# Sheet1.net
KiCad netlist of a schematic drawn in Altium Designer
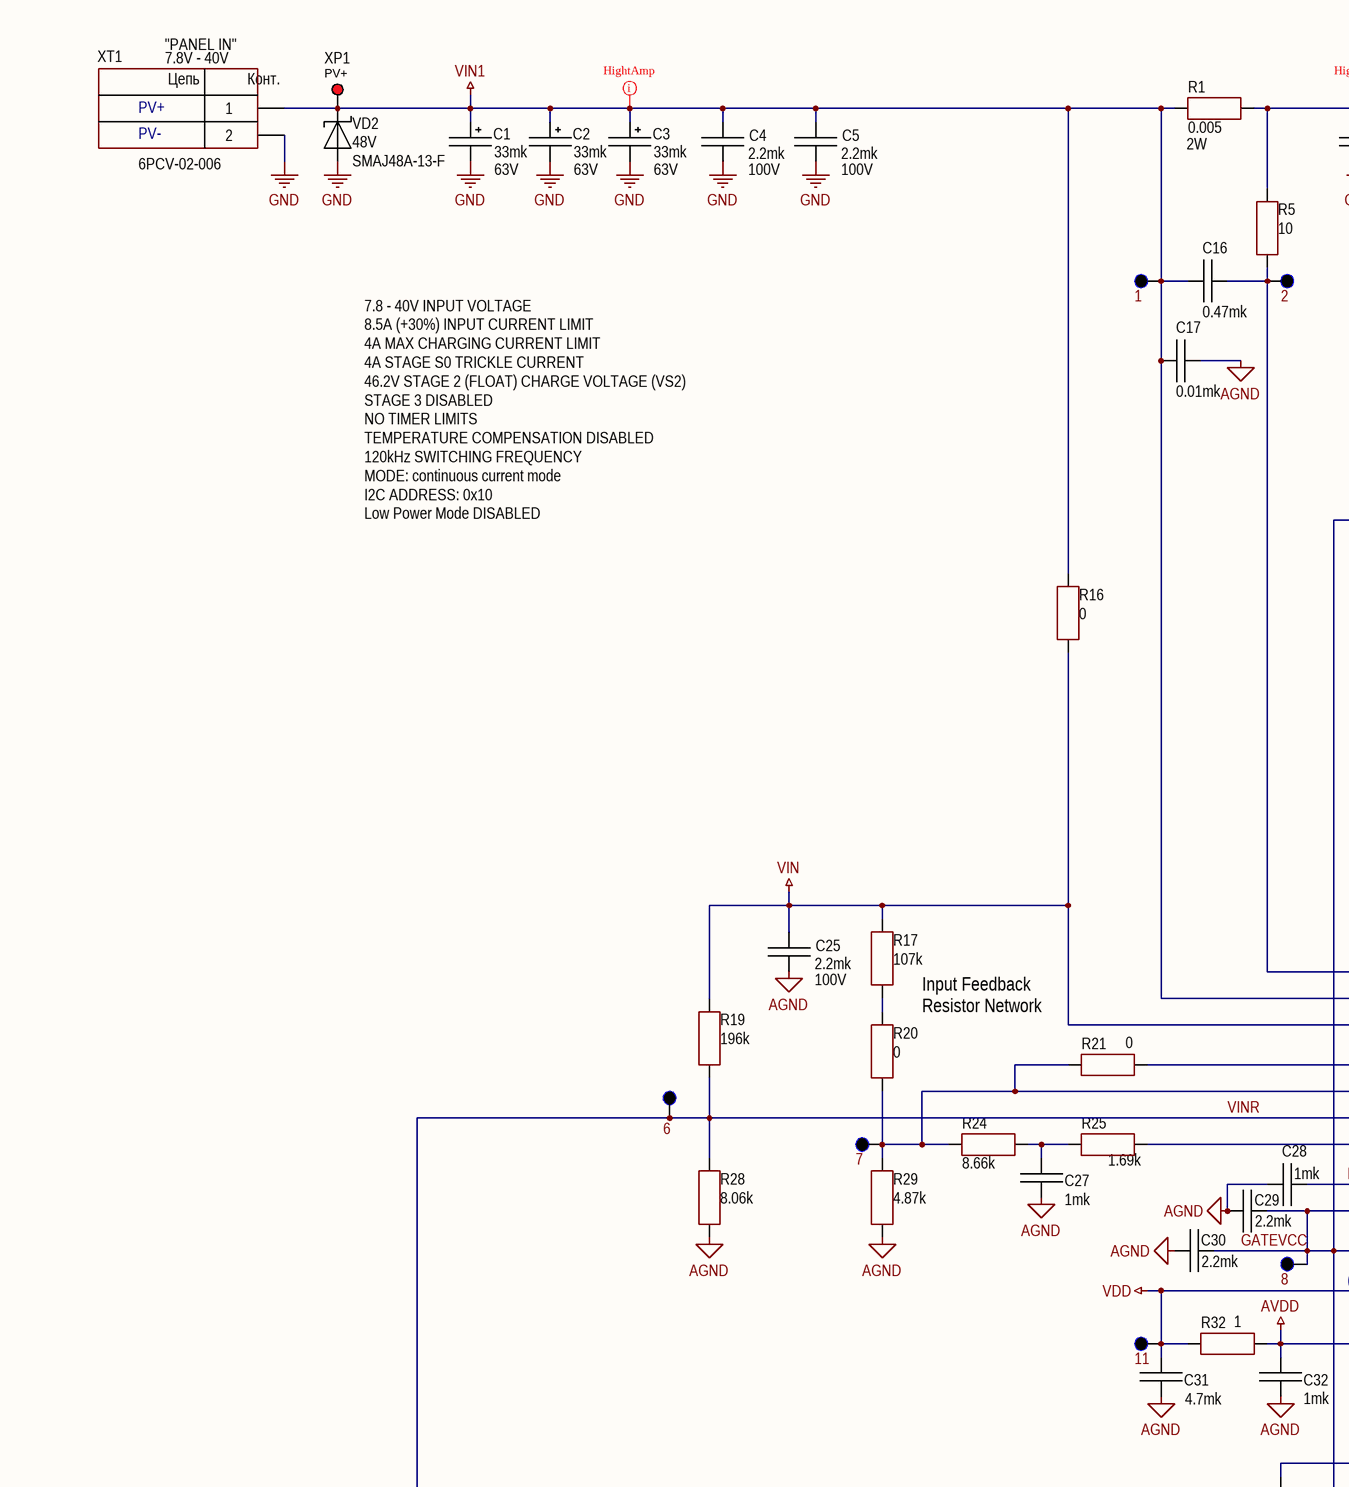
[diagram p0: Sheet1.SchDoc, top left]
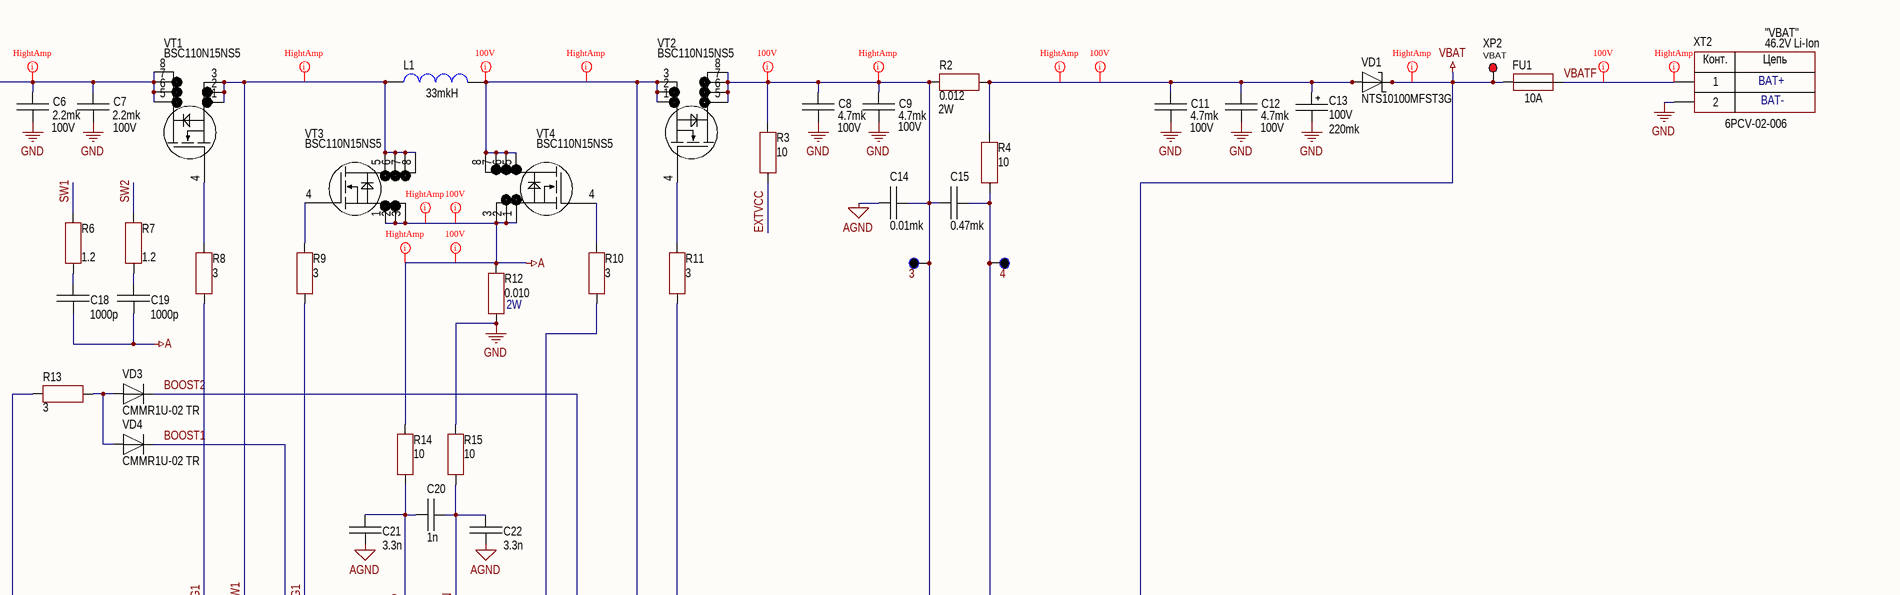
[diagram p1: Sheet1.SchDoc, top right]
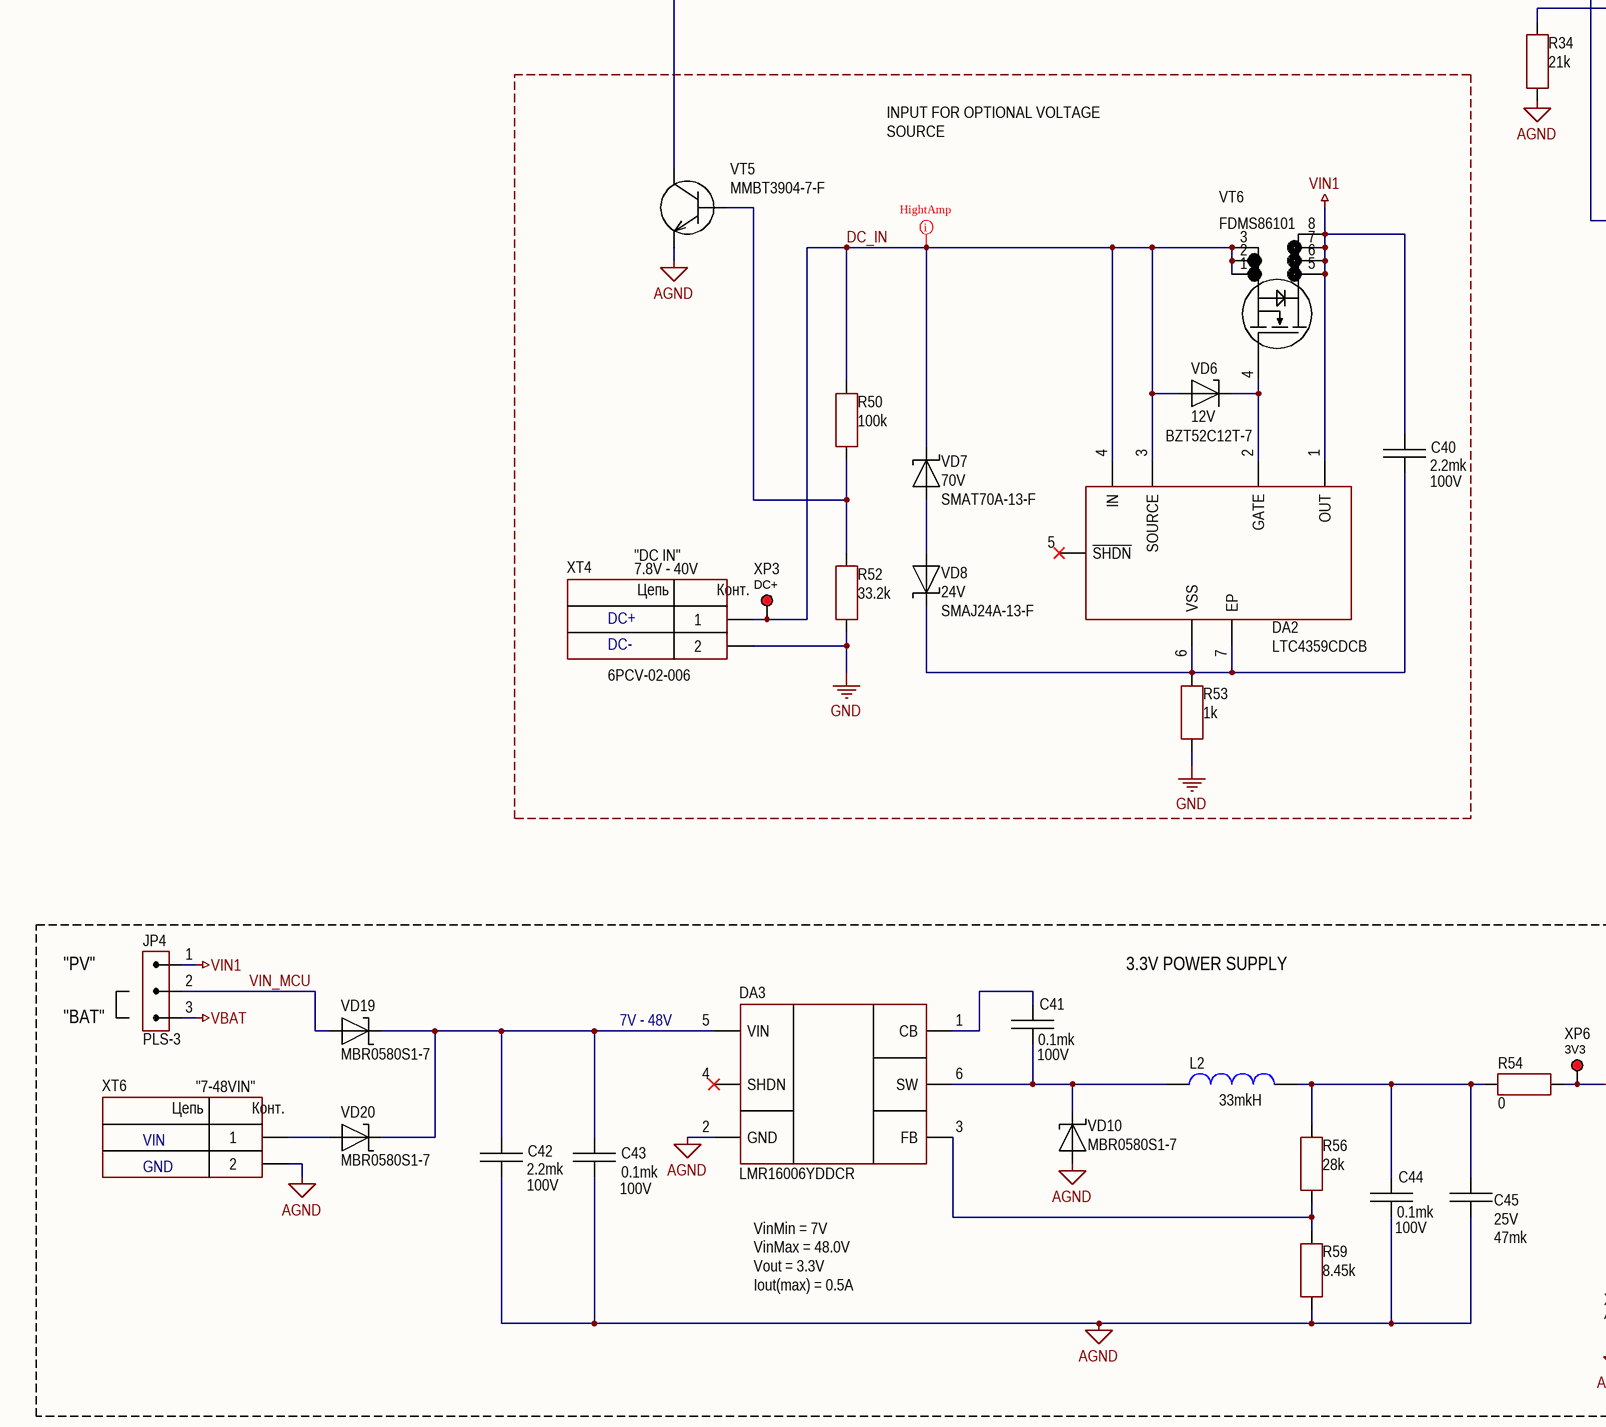
[diagram p2: Sheet1.SchDoc, bottom left]
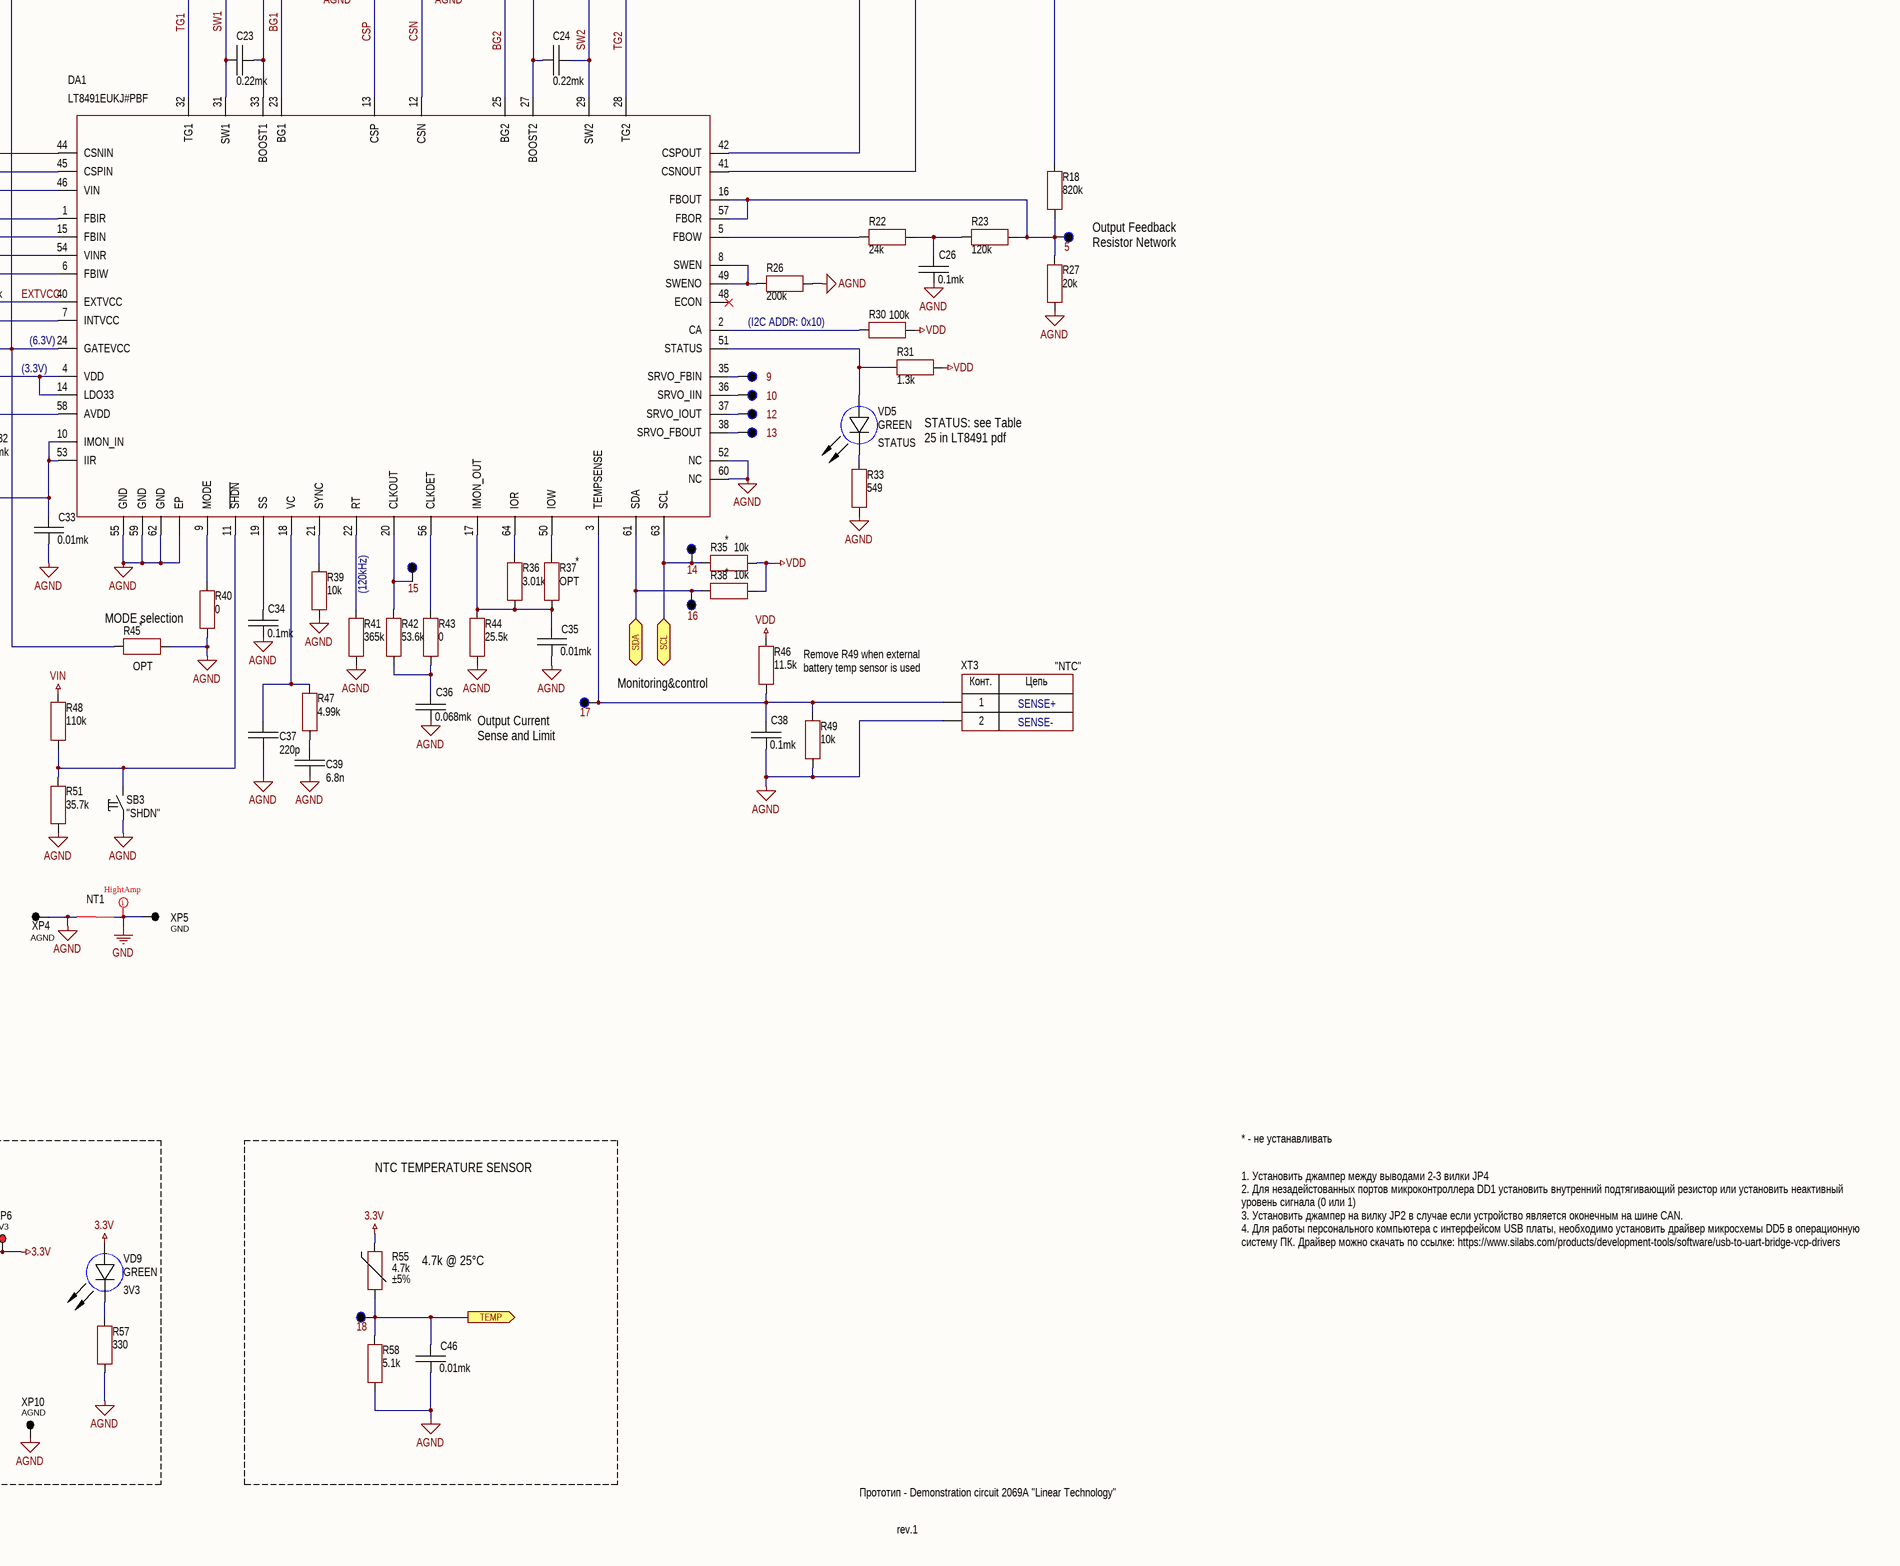
[diagram p3: Sheet1.SchDoc, bottom right]

(export (version "E")
  (design (tool "Eeschema 10.0.6"))
  (components
    (comp (ref "1")
      (value "test")
      (footprint "TEST_point_SMD")
      (description "Контактная площадка без компонента")
      (libsource (lib "Connector") (part "TEST point"))
    )
    (comp (ref "2")
      (value "test")
      (footprint "TEST_point_SMD")
      (description "Контактная площадка без компонента")
      (libsource (lib "Connector") (part "TEST point"))
    )
    (comp (ref "3")
      (value "test")
      (footprint "TEST_point_SMD")
      (description "Контактная площадка без компонента")
      (libsource (lib "Connector") (part "TEST point"))
    )
    (comp (ref "4")
      (value "test")
      (footprint "TEST_point_SMD")
      (description "Контактная площадка без компонента")
      (libsource (lib "Connector") (part "TEST point"))
    )
    (comp (ref "5")
      (value "test")
      (footprint "TEST_point_SMD")
      (description "Контактная площадка без компонента")
      (libsource (lib "Connector") (part "TEST point"))
    )
    (comp (ref "6")
      (value "test")
      (footprint "TEST_point_SMD")
      (description "Контактная площадка без компонента")
      (libsource (lib "Connector") (part "TEST point"))
    )
    (comp (ref "7")
      (value "test")
      (footprint "TEST_point_SMD")
      (description "Контактная площадка без компонента")
      (libsource (lib "Connector") (part "TEST point"))
    )
    (comp (ref "8")
      (value "test")
      (footprint "TEST_point_SMD")
      (description "Контактная площадка без компонента")
      (libsource (lib "Connector") (part "TEST point"))
    )
    (comp (ref "9")
      (value "test")
      (footprint "TEST_point_SMD")
      (description "Контактная площадка без компонента")
      (libsource (lib "Connector") (part "TEST point"))
    )
    (comp (ref "10")
      (value "test")
      (footprint "TEST_point_SMD")
      (description "Контактная площадка без компонента")
      (libsource (lib "Connector") (part "TEST point"))
    )
    (comp (ref "11")
      (value "test")
      (footprint "TEST_point_SMD")
      (description "Контактная площадка без компонента")
      (libsource (lib "Connector") (part "TEST point"))
    )
    (comp (ref "12")
      (value "test")
      (footprint "TEST_point_SMD")
      (description "Контактная площадка без компонента")
      (libsource (lib "Connector") (part "TEST point"))
    )
    (comp (ref "13")
      (value "test")
      (footprint "TEST_point_SMD")
      (description "Контактная площадка без компонента")
      (libsource (lib "Connector") (part "TEST point"))
    )
    (comp (ref "14")
      (value "test")
      (footprint "TEST_point_SMD")
      (description "Контактная площадка без компонента")
      (libsource (lib "Connector") (part "TEST point"))
    )
    (comp (ref "15")
      (value "test")
      (footprint "TEST_point_SMD")
      (description "Контактная площадка без компонента")
      (libsource (lib "Connector") (part "TEST point"))
    )
    (comp (ref "16")
      (value "test")
      (footprint "TEST_point_SMD")
      (description "Контактная площадка без компонента")
      (libsource (lib "Connector") (part "TEST point"))
    )
    (comp (ref "17")
      (value "test")
      (footprint "TEST_point_SMD")
      (description "Контактная площадка без компонента")
      (libsource (lib "Connector") (part "TEST point"))
    )
    (comp (ref "18")
      (value "test")
      (footprint "TEST_point_SMD")
      (description "Контактная площадка без компонента")
      (libsource (lib "Connector") (part "TEST point"))
    )
    (comp (ref "C1")
      (value "33mk")
      (footprint "PCB_MPPT:CAP: EEH-ZA_SIZE-F")
      (fields
        (field (name "MANUFACTURER") "Panasonic")
        (field (name "PARTNUMBER") "EEH-ZA1J330P")
        (field (name "VALUEMANUFACTURERPARTNUMBER") "EP-cap, 33mk, 63V, ±20%")
        (field (name "VOLTAGE") "63V")
      )
      (libsource (lib "Capacitor") (part "Aluminium"))
    )
    (comp (ref "C2")
      (value "33mk")
      (footprint "PCB_MPPT:CAP: EEH-ZA_SIZE-F")
      (fields
        (field (name "MANUFACTURER") "Panasonic")
        (field (name "PARTNUMBER") "EEH-ZA1J330P")
        (field (name "VALUEMANUFACTURERPARTNUMBER") "EP-cap, 33mk, 63V, ±20%")
        (field (name "VOLTAGE") "63V")
      )
      (libsource (lib "Capacitor") (part "Aluminium"))
    )
    (comp (ref "C3")
      (value "33mk")
      (footprint "PCB_MPPT:CAP: EEH-ZA_SIZE-F")
      (fields
        (field (name "MANUFACTURER") "Panasonic")
        (field (name "PARTNUMBER") "EEH-ZA1J330P")
        (field (name "VALUEMANUFACTURERPARTNUMBER") "EP-cap, 33mk, 63V, ±20%")
        (field (name "VOLTAGE") "63V")
      )
      (libsource (lib "Capacitor") (part "Aluminium"))
    )
    (comp (ref "C4")
      (value "2.2mk")
      (footprint "PCB_MPPT:CAP: 1210")
      (fields
        (field (name "MANUFACTURER") "AVX")
        (field (name "PARTNUMBER") "12101C225KAT2A")
        (field (name "VALUEMANUFACTURERPARTNUMBER") "CAP CER, 2.2mk, X7R, ±10%, 100V, 1210")
        (field (name "VOLTAGE") "100V")
      )
      (libsource (lib "Capacitor") (part "Ceramic_1210"))
    )
    (comp (ref "C5")
      (value "2.2mk")
      (footprint "PCB_MPPT:CAP: 1210")
      (fields
        (field (name "MANUFACTURER") "AVX")
        (field (name "PARTNUMBER") "12101C225KAT2A")
        (field (name "VALUEMANUFACTURERPARTNUMBER") "CAP CER, 2.2mk, X7R, ±10%, 100V, 1210")
        (field (name "VOLTAGE") "100V")
      )
      (libsource (lib "Capacitor") (part "Ceramic_1210"))
    )
    (comp (ref "C6")
      (value "2.2mk")
      (footprint "PCB_MPPT:CAP: 1210")
      (fields
        (field (name "MANUFACTURER") "AVX")
        (field (name "PARTNUMBER") "12101C225KAT2A")
        (field (name "VALUEMANUFACTURERPARTNUMBER") "CAP CER, 2.2mk, X7R, ±10%, 100V, 1210")
        (field (name "VOLTAGE") "100V")
      )
      (libsource (lib "Capacitor") (part "Ceramic_1210"))
    )
    (comp (ref "C7")
      (value "2.2mk")
      (footprint "PCB_MPPT:CAP: 1210")
      (fields
        (field (name "MANUFACTURER") "AVX")
        (field (name "PARTNUMBER") "12101C225KAT2A")
        (field (name "VALUEMANUFACTURERPARTNUMBER") "CAP CER, 2.2mk, X7R, ±10%, 100V, 1210")
        (field (name "VOLTAGE") "100V")
      )
      (libsource (lib "Capacitor") (part "Ceramic_1210"))
    )
    (comp (ref "C8")
      (value "4.7mk")
      (footprint "PCB_MPPT:CAP: 1812")
      (fields
        (field (name "MANUFACTURER") "TDK")
        (field (name "PARTNUMBER") "C4532X7S2A475M230KB")
        (field (name "VALUEMANUFACTURERPARTNUMBER") "CAP CER, 4.7mk, X7S, ±20%, 100V, 1812")
        (field (name "VOLTAGE") "100V")
      )
      (libsource (lib "Capacitor") (part "Ceramic_1812"))
    )
    (comp (ref "C9")
      (value "4.7mk")
      (footprint "PCB_MPPT:CAP: 1812")
      (fields
        (field (name "MANUFACTURER") "TDK")
        (field (name "PARTNUMBER") "C4532X7S2A475M230KB")
        (field (name "VALUEMANUFACTURERPARTNUMBER") "CAP CER, 4.7mk, X7S, ±20%, 100V, 1812")
        (field (name "VOLTAGE") "100V")
      )
      (libsource (lib "Capacitor") (part "Ceramic_1812"))
    )
    (comp (ref "C11")
      (value "4.7mk")
      (footprint "PCB_MPPT:CAP: 1812")
      (fields
        (field (name "MANUFACTURER") "TDK")
        (field (name "PARTNUMBER") "C4532X7S2A475M230KB")
        (field (name "VALUEMANUFACTURERPARTNUMBER") "CAP CER, 4.7mk, X7S, ±20%, 100V, 1812")
        (field (name "VOLTAGE") "100V")
      )
      (libsource (lib "Capacitor") (part "Ceramic_1812"))
    )
    (comp (ref "C12")
      (value "4.7mk")
      (footprint "PCB_MPPT:CAP: 1812")
      (fields
        (field (name "MANUFACTURER") "TDK")
        (field (name "PARTNUMBER") "C4532X7S2A475M230KB")
        (field (name "VALUEMANUFACTURERPARTNUMBER") "CAP CER, 4.7mk, X7S, ±20%, 100V, 1812")
        (field (name "VOLTAGE") "100V")
      )
      (libsource (lib "Capacitor") (part "Ceramic_1812"))
    )
    (comp (ref "C13")
      (value "220mk")
      (footprint "PCB_MPPT:CAP: D13C5H25")
      (fields
        (field (name "MANUFACTURER") "United Chemi-Con")
        (field (name "PARTNUMBER") "EKZE101ELL221MK25S")
        (field (name "VALUEMANUFACTURERPARTNUMBER") "CAP ALUM, 220mk, 100V, ±20%")
        (field (name "VOLTAGE") "100V")
      )
      (libsource (lib "Capacitor") (part "Aluminium"))
    )
    (comp (ref "C14")
      (value "0.01mk")
      (footprint "PCB_MPPT:CAP: 0603")
      (fields
        (field (name "MANUFACTURER") "AVX")
        (field (name "PARTNUMBER") "06031C103KAT2A")
        (field (name "VALUEMANUFACTURERPARTNUMBER") "CAP CER, 0.01mk, X7R, ±10%, 100V, 0603")
      )
      (libsource (lib "Capacitor") (part "Ceramic_0603"))
    )
    (comp (ref "C15")
      (value "0.47mk")
      (footprint "PCB_MPPT:CAP: 0603")
      (fields
        (field (name "MANUFACTURER") "Murata")
        (field (name "PARTNUMBER") "GRM188R71C474KA88D")
        (field (name "VALUEMANUFACTURERPARTNUMBER") "CAP CER, 0.47mk, X7R, ±10%, 16V, 0603")
      )
      (libsource (lib "Capacitor") (part "Ceramic_0603"))
    )
    (comp (ref "C16")
      (value "0.47mk")
      (footprint "PCB_MPPT:CAP: 0603")
      (fields
        (field (name "MANUFACTURER") "Murata")
        (field (name "PARTNUMBER") "GRM188R71C474KA88D")
        (field (name "VALUEMANUFACTURERPARTNUMBER") "CAP CER, 0.47mk, X7R, ±10%, 16V, 0603")
      )
      (libsource (lib "Capacitor") (part "Ceramic_0603"))
    )
    (comp (ref "C17")
      (value "0.01mk")
      (footprint "PCB_MPPT:CAP: 0603")
      (fields
        (field (name "MANUFACTURER") "AVX")
        (field (name "PARTNUMBER") "06031C103KAT2A")
        (field (name "VALUEMANUFACTURERPARTNUMBER") "CAP CER, 0.01mk, X7R, ±10%, 100V, 0603")
      )
      (libsource (lib "Capacitor") (part "Ceramic_0603"))
    )
    (comp (ref "C18")
      (value "1000p")
      (footprint "PCB_MPPT:CAP: 1206")
      (fields
        (field (name "MANUFACTURER") "AVX")
        (field (name "PARTNUMBER") "12061A102KAT2A")
        (field (name "VALUEMANUFACTURERPARTNUMBER") "CAP CER, 1000p, NP0, ±10%, 100V, 1206")
      )
      (libsource (lib "Capacitor") (part "Ceramic_1206"))
    )
    (comp (ref "C19")
      (value "1000p")
      (footprint "PCB_MPPT:CAP: 1206")
      (fields
        (field (name "MANUFACTURER") "AVX")
        (field (name "PARTNUMBER") "12061A102KAT2A")
        (field (name "VALUEMANUFACTURERPARTNUMBER") "CAP CER, 1000p, NP0, ±10%, 100V, 1206")
      )
      (libsource (lib "Capacitor") (part "Ceramic_1206"))
    )
    (comp (ref "C20")
      (value "1n")
      (footprint "PCB_MPPT:CAP: 0603")
      (fields
        (field (name "MANUFACTURER") "AVX")
        (field (name "PARTNUMBER") "0603YC102MAT4A")
        (field (name "VALUEMANUFACTURERPARTNUMBER") "CAP CER, 1n, X7R, ±20%, 16V, 0603")
      )
      (libsource (lib "Capacitor") (part "Ceramic_0603"))
    )
    (comp (ref "C21")
      (value "3.3n")
      (footprint "PCB_MPPT:CAP: 0603")
      (fields
        (field (name "MANUFACTURER") "AVX")
        (field (name "PARTNUMBER") "0603YC332MAT4A")
        (field (name "VALUEMANUFACTURERPARTNUMBER") "CAP CER, 3.3n, X7R, ±20%, 16V, 0603")
      )
      (libsource (lib "Capacitor") (part "Ceramic_0603"))
    )
    (comp (ref "C22")
      (value "3.3n")
      (footprint "PCB_MPPT:CAP: 0603")
      (fields
        (field (name "MANUFACTURER") "AVX")
        (field (name "PARTNUMBER") "0603YC332MAT4A")
        (field (name "VALUEMANUFACTURERPARTNUMBER") "CAP CER, 3.3n, X7R, ±20%, 16V, 0603")
      )
      (libsource (lib "Capacitor") (part "Ceramic_0603"))
    )
    (comp (ref "C23")
      (value "0.22mk")
      (footprint "PCB_MPPT:CAP: 0603")
      (fields
        (field (name "MANUFACTURER") "AVX")
        (field (name "PARTNUMBER") "0603YD224KAT2A")
        (field (name "VALUEMANUFACTURERPARTNUMBER") "CAP CER, 0.22mk, X5R, ±20%, 16V, 0603")
      )
      (libsource (lib "Capacitor") (part "Ceramic_0603"))
    )
    (comp (ref "C24")
      (value "0.22mk")
      (footprint "PCB_MPPT:CAP: 0603")
      (fields
        (field (name "MANUFACTURER") "AVX")
        (field (name "PARTNUMBER") "0603YD224KAT2A")
        (field (name "VALUEMANUFACTURERPARTNUMBER") "CAP CER, 0.22mk, X5R, ±20%, 16V, 0603")
      )
      (libsource (lib "Capacitor") (part "Ceramic_0603"))
    )
    (comp (ref "C25")
      (value "2.2mk")
      (footprint "PCB_MPPT:CAP: 1210")
      (fields
        (field (name "MANUFACTURER") "AVX")
        (field (name "PARTNUMBER") "12101C225KAT2A")
        (field (name "VALUEMANUFACTURERPARTNUMBER") "CAP CER, 2.2mk, X7R, ±10%, 100V, 1210")
        (field (name "VOLTAGE") "100V")
      )
      (libsource (lib "Capacitor") (part "Ceramic_1210"))
    )
    (comp (ref "C26")
      (value "0.1mk")
      (footprint "PCB_MPPT:CAP: 0603")
      (fields
        (field (name "MANUFACTURER") "AVX")
        (field (name "PARTNUMBER") "06031C104KAT2A")
        (field (name "VALUEMANUFACTURERPARTNUMBER") "CAP CER, 0.1mk, X7R, ±10%, 100V, 0603")
      )
      (libsource (lib "Capacitor") (part "Ceramic_0603"))
    )
    (comp (ref "C27")
      (value "1mk")
      (footprint "PCB_MPPT:CAP: 0603")
      (fields
        (field (name "MANUFACTURER") "AVX")
        (field (name "PARTNUMBER") "0603YC105KAT2A")
        (field (name "VALUEMANUFACTURERPARTNUMBER") "CAP CER, 1mk, X7R, ±10%, 16V, 0603")
      )
      (libsource (lib "Capacitor") (part "Ceramic_0603"))
    )
    (comp (ref "C28")
      (value "1mk")
      (footprint "PCB_MPPT:CAP: 1210")
      (fields
        (field (name "MANUFACTURER") "AVX")
        (field (name "PARTNUMBER") "12101C105KAT2A")
        (field (name "VALUEMANUFACTURERPARTNUMBER") "CAP CER, 1mk, X7R, ±10%, 100V, 1210")
      )
      (libsource (lib "Capacitor") (part "Ceramic_1210"))
    )
    (comp (ref "C29")
      (value "2.2mk")
      (footprint "PCB_MPPT:CAP: 0603")
      (fields
        (field (name "MANUFACTURER") "AVX")
        (field (name "PARTNUMBER") "0603ZD225KAT2A")
        (field (name "VALUEMANUFACTURERPARTNUMBER") "CAP CER, 2.2mk, X5R, ±10%, 10V, 0603")
      )
      (libsource (lib "Capacitor") (part "Ceramic_0603"))
    )
    (comp (ref "C30")
      (value "2.2mk")
      (footprint "PCB_MPPT:CAP: 0603")
      (fields
        (field (name "MANUFACTURER") "AVX")
        (field (name "PARTNUMBER") "0603ZD225KAT2A")
        (field (name "VALUEMANUFACTURERPARTNUMBER") "CAP CER, 2.2mk, X5R, ±10%, 10V, 0603")
      )
      (libsource (lib "Capacitor") (part "Ceramic_0603"))
    )
    (comp (ref "C31")
      (value "4.7mk")
      (footprint "PCB_MPPT:CAP: 0805")
      (fields
        (field (name "MANUFACTURER") "AVX")
        (field (name "PARTNUMBER") "0805YC475KAT2A")
        (field (name "VALUEMANUFACTURERPARTNUMBER") "CAP CER, 4.7mk, X7R, ±10%, 16V, 0805")
      )
      (libsource (lib "Capacitor") (part "Ceramic_0805"))
    )
    (comp (ref "C32")
      (value "1mk")
      (footprint "PCB_MPPT:CAP: 0603")
      (fields
        (field (name "MANUFACTURER") "AVX")
        (field (name "PARTNUMBER") "0603YC105KAT2A")
        (field (name "VALUEMANUFACTURERPARTNUMBER") "CAP CER, 1mk, X7R, ±10%, 16V, 0603")
      )
      (libsource (lib "Capacitor") (part "Ceramic_0603"))
    )
    (comp (ref "C33")
      (value "0.01mk")
      (footprint "PCB_MPPT:CAP: 0603")
      (fields
        (field (name "MANUFACTURER") "AVX")
        (field (name "PARTNUMBER") "06031C103KAT2A")
        (field (name "VALUEMANUFACTURERPARTNUMBER") "CAP CER, 0.01mk, X7R, ±10%, 100V, 0603")
      )
      (libsource (lib "Capacitor") (part "Ceramic_0603"))
    )
    (comp (ref "C34")
      (value "0.1mk")
      (footprint "PCB_MPPT:CAP: 0603")
      (fields
        (field (name "MANUFACTURER") "AVX")
        (field (name "PARTNUMBER") "06031C104KAT2A")
        (field (name "VALUEMANUFACTURERPARTNUMBER") "CAP CER, 0.1mk, X7R, ±10%, 100V, 0603")
      )
      (libsource (lib "Capacitor") (part "Ceramic_0603"))
    )
    (comp (ref "C35")
      (value "0.01mk")
      (footprint "PCB_MPPT:CAP: 0603")
      (fields
        (field (name "MANUFACTURER") "AVX")
        (field (name "PARTNUMBER") "06031C103KAT2A")
        (field (name "VALUEMANUFACTURERPARTNUMBER") "CAP CER, 0.01mk, X7R, ±10%, 100V, 0603")
      )
      (libsource (lib "Capacitor") (part "Ceramic_0603"))
    )
    (comp (ref "C36")
      (value "0.068mk")
      (footprint "PCB_MPPT:CAP: 0603")
      (fields
        (field (name "MANUFACTURER") "AVX")
        (field (name "PARTNUMBER") "0603YC683KAT2A")
        (field (name "VALUEMANUFACTURERPARTNUMBER") "CAP CER, 0.068mk, X7R, ±10%, 16V, 0603")
      )
      (libsource (lib "Capacitor") (part "Ceramic_0603"))
    )
    (comp (ref "C37")
      (value "220p")
      (footprint "PCB_MPPT:CAP: 0603")
      (fields
        (field (name "MANUFACTURER") "AVX")
        (field (name "PARTNUMBER") "06033A221JAT2A")
        (field (name "VALUEMANUFACTURERPARTNUMBER") "CAP CER, 220p, X7R, ±5%, 25V, 0603")
      )
      (libsource (lib "Capacitor") (part "Ceramic_0603"))
    )
    (comp (ref "C38")
      (value "0.1mk")
      (footprint "PCB_MPPT:CAP: 0603")
      (fields
        (field (name "MANUFACTURER") "AVX")
        (field (name "PARTNUMBER") "06031C104KAT2A")
        (field (name "VALUEMANUFACTURERPARTNUMBER") "CAP CER, 0.1mk, X7R, ±10%, 100V, 0603")
      )
      (libsource (lib "Capacitor") (part "Ceramic_0603"))
    )
    (comp (ref "C39")
      (value "6.8n")
      (footprint "PCB_MPPT:CAP: 0603")
      (fields
        (field (name "MANUFACTURER") "AVX")
        (field (name "PARTNUMBER") "06035C682KAT2A")
        (field (name "VALUEMANUFACTURERPARTNUMBER") "CAP CER, 6.8n, X7R, ±10%, 50V, 0603")
      )
      (libsource (lib "Capacitor") (part "Ceramic_0603"))
    )
    (comp (ref "C40")
      (value "2.2mk")
      (footprint "PCB_MPPT:CAP: 1210")
      (fields
        (field (name "MANUFACTURER") "AVX")
        (field (name "PARTNUMBER") "12101C225KAT2A")
        (field (name "VALUEMANUFACTURERPARTNUMBER") "CAP CER, 2.2mk, X7R, ±10%, 100V, 1210")
        (field (name "VOLTAGE") "100V")
      )
      (libsource (lib "Capacitor") (part "Ceramic_1210"))
    )
    (comp (ref "C41")
      (value "0.1mk")
      (footprint "PCB_MPPT:CAP: 0603")
      (fields
        (field (name "MANUFACTURER") "AVX")
        (field (name "PARTNUMBER") "06031C104KAT2A")
        (field (name "VALUEMANUFACTURERPARTNUMBER") "CAP CER, 0.1mk, X7R, ±10%, 100V, 0603")
        (field (name "VOLTAGE") "100V")
      )
      (libsource (lib "Capacitor") (part "Ceramic_0603"))
    )
    (comp (ref "C42")
      (value "2.2mk")
      (footprint "PCB_MPPT:CAP: 1210")
      (fields
        (field (name "MANUFACTURER") "AVX")
        (field (name "PARTNUMBER") "12101C225KAT2A")
        (field (name "VALUEMANUFACTURERPARTNUMBER") "CAP CER, 2.2mk, X7R, ±10%, 100V, 1210")
        (field (name "VOLTAGE") "100V")
      )
      (libsource (lib "Capacitor") (part "Ceramic_1210"))
    )
    (comp (ref "C43")
      (value "0.1mk")
      (footprint "PCB_MPPT:CAP: 0603")
      (fields
        (field (name "MANUFACTURER") "AVX")
        (field (name "PARTNUMBER") "06031C104KAT2A")
        (field (name "VALUEMANUFACTURERPARTNUMBER") "CAP CER, 0.1mk, X7R, ±10%, 100V, 0603")
        (field (name "VOLTAGE") "100V")
      )
      (libsource (lib "Capacitor") (part "Ceramic_0603"))
    )
    (comp (ref "C44")
      (value "0.1mk")
      (footprint "PCB_MPPT:CAP: 0603")
      (fields
        (field (name "MANUFACTURER") "AVX")
        (field (name "PARTNUMBER") "06031C104KAT2A")
        (field (name "VALUEMANUFACTURERPARTNUMBER") "CAP CER, 0.1mk, X7R, ±10%, 100V, 0603")
        (field (name "VOLTAGE") "100V")
      )
      (libsource (lib "Capacitor") (part "Ceramic_0603"))
    )
    (comp (ref "C45")
      (value "47mk")
      (footprint "PCB_MPPT:CAP: 1206")
      (fields
        (field (name "MANUFACTURER") "TDK")
        (field (name "PARTNUMBER") "C3216X5R1E476M160AC")
        (field (name "VALUEMANUFACTURERPARTNUMBER") "CAP CER, 47mk, X5R, ±10%, 25V, 1206")
        (field (name "VOLTAGE") "25V")
      )
      (libsource (lib "Capacitor") (part "Ceramic_1206"))
    )
    (comp (ref "C46")
      (value "0.01mk")
      (footprint "PCB_MPPT:CAP: 0603")
      (fields
        (field (name "MANUFACTURER") "AVX")
        (field (name "PARTNUMBER") "06031C103KAT2A")
        (field (name "VALUEMANUFACTURERPARTNUMBER") "CAP CER, 0.01mk, X7R, ±10%, 100V, 0603")
      )
      (libsource (lib "Capacitor") (part "Ceramic_0603"))
    )
    (comp (ref "DA1")
      (value "LT8491EUKJ#PBF")
      (footprint "PCB_MPPT:64-Lead Plastic QFN")
      (description "BUCK-BOOST BAT CH")
      (fields
        (field (name "MANUFACTURER") "Linear Technology")
        (field (name "PARTNUMBER") "LT8491EUKJ#PBF")
        (field (name "VALUEMANUFACTURERPARTNUMBER") "Charger IC Lead Acid 64-QFN (7x11)")
      )
      (libsource (lib "IC. Power supply") (part "LT8491EUKJ#PBF"))
    )
    (comp (ref "DA2")
      (value "~")
      (footprint "PCB_MPPT:6-DFN-6_DCB-M")
      (description "Ideal Diode Controller")
      (fields
        (field (name "MANUFACTURER") "Linear Technology/Analog Devices")
        (field (name "VALUEMANUFACTURERPARTNUMBER") "IC, Ideal Diode Controller, 6-DFN (2x3)")
        (field (name "PARTNUMBER") "LTC4359CDCB")
      )
      (libsource (lib "IC. Power supply") (part "LTC4359CDCB"))
    )
    (comp (ref "DA3")
      (value "~")
      (footprint "StandardCase:SOT23-6 Thin")
      (description "Buck converter")
      (fields
        (field (name "MANUFACTURER") "Texas Instruments")
        (field (name "VALUEMANUFACTURERPARTNUMBER") "DC/DC buck converter, SOT23-6")
        (field (name "PARTNUMBER") "LMR16006YDDCR")
      )
      (libsource (lib "IC. Power supply") (part "LMR16006YDDCR"))
    )
    (comp (ref "FU1")
      (value "10A")
      (footprint "PCB_MPPT:FUSE: 01110501Z (5x20 mm)")
      (fields
        (field (name "MANUFACTURER") "Littelfuse")
        (field (name "VALUEMANUFACTURERPARTNUMBER") "FUSE CLIP, 250VAC, 10A, 5x20mm")
        (field (name "PARTNUMBER") "01110506Z")
      )
      (libsource (lib "Electromechanics") (part "Fuse"))
    )
    (comp (ref "JP4")
      (value "~")
      (footprint "CustomCase:CON: PLS-3")
      (description "PLS-3")
      (fields
        (field (name "MANUFACTURER") "Connfly")
        (field (name "VALUEMANUFACTURERPARTNUMBER") "PLS-3 SINGLE ROW, 3pin, 2.54mm, 500VAC, 3A")
        (field (name "COMMENTTEXT") "PLS-3")
      )
      (libsource (lib "Connector") (part "Jumper_3pin"))
    )
    (comp (ref "L1")
      (value "33mkH")
      (footprint "PCB_MPPT:IND: WE-HCF_2013")
      (fields
        (field (name "MANUFACTURER") "Würth Elektronik")
        (field (name "PARTNUMBER") "7443633300")
        (field (name "VALUEMANUFACTURERPARTNUMBER") "Fixed inductor, 33mkH, ±15%, SMD Shielded, Ferrite (MnZn), , 12A")
      )
      (libsource (lib "Inductor") (part "Inductor_R22.9/14/7.62"))
    )
    (comp (ref "L2")
      (value "33mkH")
      (footprint "PCB_MPPT:IND: SRU8043")
      (fields
        (field (name "MANUFACTURER") "Bourns Inc.")
        (field (name "PARTNUMBER") "SRU8043-330Y")
        (field (name "VALUEMANUFACTURERPARTNUMBER") "Fixed inductor, 33mkH, ±15%, SMD Nonstandard, Ferrite, , 1.7A")
      )
      (libsource (lib "Inductor") (part "Inductor_R22.9/14/7.62"))
    )
    (comp (ref "NT1")
      (value "~")
      (footprint "PCB_MPPT:NetTie_0805_2")
      (libsource (lib "Connector") (part "NetTie"))
    )
    (comp (ref "R1")
      (value "0.005")
      (footprint "PCB_MPPT:RES: 2512")
      (fields
        (field (name "MANUFACTURER") "Vishay")
        (field (name "PARTNUMBER") "WSL25125L000FEA18")
        (field (name "VALUEMANUFACTURERPARTNUMBER") "Res, SMD, 0.005, ±1%, 2512, 2W")
        (field (name "POWER") "2W")
      )
      (libsource (lib "") (part "Resistor_2512_1"))
    )
    (comp (ref "R2")
      (value "0.012")
      (footprint "PCB_MPPT:RES: 2512")
      (fields
        (field (name "MANUFACTURER") "Vishay")
        (field (name "PARTNUMBER") "WSL2512R0250FEA18")
        (field (name "VALUEMANUFACTURERPARTNUMBER") "Res, SMD, 0.012, ±1%, 2512, 2W")
        (field (name "POWER") "2W")
      )
      (libsource (lib "") (part "Resistor_2512_1"))
    )
    (comp (ref "R3")
      (value "10")
      (footprint "PCB_MPPT:RES: 0603")
      (fields
        (field (name "MANUFACTURER") "Vishay")
        (field (name "PARTNUMBER") "CRCW060310R0JNEAC")
        (field (name "VALUEMANUFACTURERPARTNUMBER") "Res, SMD, 10, ±5%, 0603, 0.1W")
      )
      (libsource (lib "") (part "Resistor_0603_1"))
    )
    (comp (ref "R4")
      (value "10")
      (footprint "PCB_MPPT:RES: 0603")
      (fields
        (field (name "MANUFACTURER") "Vishay")
        (field (name "PARTNUMBER") "CRCW060310R0JNEAC")
        (field (name "VALUEMANUFACTURERPARTNUMBER") "Res, SMD, 10, ±5%, 0603, 0.1W")
      )
      (libsource (lib "") (part "Resistor_0603_1"))
    )
    (comp (ref "R5")
      (value "10")
      (footprint "PCB_MPPT:RES: 0603")
      (fields
        (field (name "MANUFACTURER") "Vishay")
        (field (name "PARTNUMBER") "CRCW060310R0JNEAC")
        (field (name "VALUEMANUFACTURERPARTNUMBER") "Res, SMD, 10, ±5%, 0603, 0.1W")
      )
      (libsource (lib "") (part "Resistor_0603_1"))
    )
    (comp (ref "R6")
      (value "1.2")
      (footprint "PCB_MPPT:RES: 1206")
      (fields
        (field (name "MANUFACTURER") "Vishay")
        (field (name "PARTNUMBER") "CRCW12061R20FKEA")
        (field (name "VALUEMANUFACTURERPARTNUMBER") "Resistor film, 1.2, ±5%, 1206, 0.25W")
      )
      (libsource (lib "Resistor") (part "Resistor_1206"))
    )
    (comp (ref "R7")
      (value "1.2")
      (footprint "PCB_MPPT:RES: 1206")
      (fields
        (field (name "MANUFACTURER") "Vishay")
        (field (name "PARTNUMBER") "CRCW12061R20FKEA")
        (field (name "VALUEMANUFACTURERPARTNUMBER") "Resistor film, 1.2, ±5%, 1206, 0.25W")
      )
      (libsource (lib "Resistor") (part "Resistor_1206"))
    )
    (comp (ref "R8")
      (value "3")
      (footprint "PCB_MPPT:RES: 0603")
      (fields
        (field (name "MANUFACTURER") "Vishay")
        (field (name "PARTNUMBER") "CRCW06033R00JNEA")
        (field (name "VALUEMANUFACTURERPARTNUMBER") "Res, SMD, 3, ±5%, 0603, 0.1W")
      )
      (libsource (lib "Resistor") (part "Resistor_0603"))
    )
    (comp (ref "R9")
      (value "3")
      (footprint "PCB_MPPT:RES: 0603")
      (fields
        (field (name "MANUFACTURER") "Vishay")
        (field (name "PARTNUMBER") "CRCW06033R00JNEA")
        (field (name "VALUEMANUFACTURERPARTNUMBER") "Res, SMD, 3, ±5%, 0603, 0.1W")
      )
      (libsource (lib "Resistor") (part "Resistor_0603"))
    )
    (comp (ref "R10")
      (value "3")
      (footprint "PCB_MPPT:RES: 0603")
      (fields
        (field (name "MANUFACTURER") "Vishay")
        (field (name "PARTNUMBER") "CRCW06033R00JNEA")
        (field (name "VALUEMANUFACTURERPARTNUMBER") "Res, SMD, 3, ±5%, 0603, 0.1W")
      )
      (libsource (lib "Resistor") (part "Resistor_0603"))
    )
    (comp (ref "R11")
      (value "3")
      (footprint "PCB_MPPT:RES: 0603")
      (fields
        (field (name "MANUFACTURER") "Vishay")
        (field (name "PARTNUMBER") "CRCW06033R00JNEA")
        (field (name "VALUEMANUFACTURERPARTNUMBER") "Res, SMD, 3, ±5%, 0603, 0.1W")
      )
      (libsource (lib "Resistor") (part "Resistor_0603"))
    )
    (comp (ref "R12")
      (value "0.010")
      (footprint "PCB_MPPT:RES: 2512")
      (fields
        (field (name "MANUFACTURER") "Bourns")
        (field (name "PARTNUMBER") "CRA2512-FZ-R010ELF")
        (field (name "VALUEMANUFACTURERPARTNUMBER") "Res, SMD, 0.010, ±1%, 2512, 2W")
        (field (name "POWER") "2W")
      )
      (libsource (lib "Resistor") (part "Resistor_2512"))
    )
    (comp (ref "R13")
      (value "3")
      (footprint "PCB_MPPT:RES: 0603")
      (fields
        (field (name "MANUFACTURER") "Vishay")
        (field (name "PARTNUMBER") "CRCW06033R00JNEA")
        (field (name "VALUEMANUFACTURERPARTNUMBER") "Res, SMD, 3, ±5%, 0603, 0.1W")
      )
      (libsource (lib "") (part "Resistor_0603_3"))
    )
    (comp (ref "R14")
      (value "10")
      (footprint "PCB_MPPT:RES: 0603")
      (fields
        (field (name "MANUFACTURER") "Vishay")
        (field (name "PARTNUMBER") "CRCW060310R0JNEAC")
        (field (name "VALUEMANUFACTURERPARTNUMBER") "Res, SMD, 10, ±5%, 0603, 0.1W")
      )
      (libsource (lib "") (part "Resistor_0603_1"))
    )
    (comp (ref "R15")
      (value "10")
      (footprint "PCB_MPPT:RES: 0603")
      (fields
        (field (name "MANUFACTURER") "Vishay")
        (field (name "PARTNUMBER") "CRCW060310R0JNEAC")
        (field (name "VALUEMANUFACTURERPARTNUMBER") "Res, SMD, 10, ±5%, 0603, 0.1W")
      )
      (libsource (lib "") (part "Resistor_0603_1"))
    )
    (comp (ref "R16")
      (value "0")
      (footprint "PCB_MPPT:RES: 0603")
      (fields
        (field (name "MANUFACTURER") "Vishay")
        (field (name "PARTNUMBER") "CRCW06030000Z0EA")
        (field (name "VALUEMANUFACTURERPARTNUMBER") "Res, SMD, 0, ±1%, 0603, 0.1W")
      )
      (libsource (lib "") (part "Resistor_0603_1"))
    )
    (comp (ref "R17")
      (value "107k")
      (footprint "PCB_MPPT:RES: 0603")
      (fields
        (field (name "MANUFACTURER") "Vishay")
        (field (name "PARTNUMBER") "CRCW060391K0FKEA")
        (field (name "VALUEMANUFACTURERPARTNUMBER") "Res, SMD, 107k, ±1%, 0603, 0.1W")
      )
      (libsource (lib "") (part "Resistor_0603_1"))
    )
    (comp (ref "R18")
      (value "820k")
      (footprint "PCB_MPPT:RES: 0603")
      (fields
        (field (name "MANUFACTURER") "Vishay")
        (field (name "PARTNUMBER") "CRCW06031M00FKEA")
        (field (name "VALUEMANUFACTURERPARTNUMBER") "Res, SMD, 820k, ±1%, 0603, 0.1W")
      )
      (libsource (lib "Resistor") (part "Resistor_0603"))
    )
    (comp (ref "R19")
      (value "196k")
      (footprint "PCB_MPPT:RES: 0603")
      (fields
        (field (name "MANUFACTURER") "Vishay")
        (field (name "PARTNUMBER") "CRCW0603196KFKEA")
        (field (name "VALUEMANUFACTURERPARTNUMBER") "Res, SMD, 196k, ±1%, 0603, 0.1W")
      )
      (libsource (lib "") (part "Resistor_0603_1"))
    )
    (comp (ref "R20")
      (value "0")
      (footprint "PCB_MPPT:RES: 0603")
      (fields
        (field (name "MANUFACTURER") "Vishay")
        (field (name "PARTNUMBER") "CRCW06031K00FKEA")
        (field (name "VALUEMANUFACTURERPARTNUMBER") "Res, SMD, 0, ±1%, 0603, 0.1W")
      )
      (libsource (lib "") (part "Resistor_0603_1"))
    )
    (comp (ref "R21")
      (value "0")
      (footprint "PCB_MPPT:RES: 0603")
      (fields
        (field (name "MANUFACTURER") "Vishay")
        (field (name "PARTNUMBER") "CRCW06030000Z0EA")
        (field (name "VALUEMANUFACTURERPARTNUMBER") "Res, SMD, 0, ±1%, 0603, 0.1W")
      )
      (libsource (lib "") (part "Resistor_0603_2"))
    )
    (comp (ref "R22")
      (value "24k")
      (footprint "PCB_MPPT:RES: 0603")
      (fields
        (field (name "MANUFACTURER") "Vishay")
        (field (name "PARTNUMBER") "CRCW060322K6FKEA")
        (field (name "VALUEMANUFACTURERPARTNUMBER") "Res, SMD, 24k, ±1%, 0603, 0.1W")
      )
      (libsource (lib "") (part "Resistor_0603_3"))
    )
    (comp (ref "R23")
      (value "120k")
      (footprint "PCB_MPPT:RES: 0603")
      (fields
        (field (name "MANUFACTURER") "Vishay")
        (field (name "PARTNUMBER") "CRCW0603115KFKEA")
        (field (name "VALUEMANUFACTURERPARTNUMBER") "Res, SMD, 120k, ±1%, 0603, 0.1W")
      )
      (libsource (lib "") (part "Resistor_0603_3"))
    )
    (comp (ref "R24")
      (value "8.66k")
      (footprint "PCB_MPPT:RES: 0603")
      (fields
        (field (name "MANUFACTURER") "Vishay")
        (field (name "PARTNUMBER") "CRCW060328K0FKEAHP")
        (field (name "VALUEMANUFACTURERPARTNUMBER") "Res, SMD, 8.66k, ±1%, 0603, 0.1W")
      )
      (libsource (lib "") (part "Resistor_0603_2"))
    )
    (comp (ref "R25")
      (value "1.69k")
      (footprint "PCB_MPPT:RES: 0603")
      (fields
        (field (name "MANUFACTURER") "Vishay")
        (field (name "PARTNUMBER") "CRCW06035K60FKEA")
        (field (name "VALUEMANUFACTURERPARTNUMBER") "Res, SMD, 1.69k, ±1%, 0603, 0.1W")
      )
      (libsource (lib "") (part "Resistor_0603_2"))
    )
    (comp (ref "R26")
      (value "200k")
      (footprint "PCB_MPPT:RES: 0603")
      (fields
        (field (name "MANUFACTURER") "Vishay")
        (field (name "PARTNUMBER") "CRCW0603200KFKEAC")
        (field (name "VALUEMANUFACTURERPARTNUMBER") "Res, SMD, 200k, ±1%, 0603, 0.1W")
      )
      (libsource (lib "") (part "Resistor_0603_2"))
    )
    (comp (ref "R27")
      (value "20k")
      (footprint "PCB_MPPT:RES: 0603")
      (fields
        (field (name "MANUFACTURER") "Vishay")
        (field (name "PARTNUMBER") "CRCW060320K0FKEC")
        (field (name "VALUEMANUFACTURERPARTNUMBER") "Res, SMD, 20k, ±1%, 0603, 0.1W")
      )
      (libsource (lib "Resistor") (part "Resistor_0603"))
    )
    (comp (ref "R28")
      (value "8.06k")
      (footprint "PCB_MPPT:RES: 0603")
      (fields
        (field (name "MANUFACTURER") "Vishay")
        (field (name "PARTNUMBER") "CRCW06038K06FKEA")
        (field (name "VALUEMANUFACTURERPARTNUMBER") "Res, SMD, 8.06k, ±1%, 0603, 0.1W")
      )
      (libsource (lib "") (part "Resistor_0603_1"))
    )
    (comp (ref "R29")
      (value "4.87k")
      (footprint "PCB_MPPT:RES: 0603")
      (fields
        (field (name "MANUFACTURER") "Vishay")
        (field (name "PARTNUMBER") "CRCW060311K3FKEA")
        (field (name "VALUEMANUFACTURERPARTNUMBER") "Res, SMD, 4.87k, ±1%, 0603, 0.1W")
      )
      (libsource (lib "") (part "Resistor_0603_1"))
    )
    (comp (ref "R30")
      (value "100k")
      (footprint "PCB_MPPT:RES: 0603")
      (fields
        (field (name "MANUFACTURER") "Vishay")
        (field (name "PARTNUMBER") "CRCW0603100KFKEA")
        (field (name "VALUEMANUFACTURERPARTNUMBER") "Res, SMD, 100k, ±1%, 0603, 0.1W")
      )
      (libsource (lib "") (part "Resistor_0603_2"))
    )
    (comp (ref "R31")
      (value "1.3k")
      (footprint "PCB_MPPT:RES: 0603")
      (fields
        (field (name "MANUFACTURER") "Vishay")
        (field (name "PARTNUMBER") "CRCW06031K30FKEA")
        (field (name "VALUEMANUFACTURERPARTNUMBER") "Res, SMD, 1.3k, ±1%, 0603, 0.1W")
      )
      (libsource (lib "") (part "Resistor_0603_2"))
    )
    (comp (ref "R32")
      (value "1")
      (footprint "PCB_MPPT:RES: 0603")
      (fields
        (field (name "MANUFACTURER") "Vishay")
        (field (name "PARTNUMBER") "CRCW06031R00FKEAC")
        (field (name "VALUEMANUFACTURERPARTNUMBER") "Res, SMD, 1, ±1%, 0603, 0.1W")
      )
      (libsource (lib "") (part "Resistor_0603_2"))
    )
    (comp (ref "R33")
      (value "549")
      (footprint "PCB_MPPT:RES: 0603")
      (fields
        (field (name "MANUFACTURER") "Vishay")
        (field (name "PARTNUMBER") "CRCW0603549RFKEA")
        (field (name "VALUEMANUFACTURERPARTNUMBER") "Res, SMD, 549, ±1%, 0603, 0.1W")
      )
      (libsource (lib "Resistor") (part "Resistor_0603"))
    )
    (comp (ref "R34")
      (value "21k")
      (footprint "PCB_MPPT:RES: 0603")
      (fields
        (field (name "MANUFACTURER") "Vishay")
        (field (name "PARTNUMBER") "CRCW060321K0FKEA")
        (field (name "VALUEMANUFACTURERPARTNUMBER") "Res, SMD, 21k, ±1%, 0603, 0.1W")
      )
      (libsource (lib "Resistor") (part "Resistor_0603"))
    )
    (comp (ref "R35")
      (value "10k")
      (footprint "PCB_MPPT:RES: 0603")
      (fields
        (field (name "MANUFACTURER") "Vishay")
        (field (name "PARTNUMBER") "CRCW060310K0JNEAC")
        (field (name "VALUEMANUFACTURERPARTNUMBER") "Res, SMD, 10k, ±5%, 0603, 0.1W")
      )
      (libsource (lib "") (part "Resistor_0603_3"))
    )
    (comp (ref "R36")
      (value "3.01k")
      (footprint "PCB_MPPT:RES: 0603")
      (fields
        (field (name "MANUFACTURER") "Vishay")
        (field (name "PARTNUMBER") "CRCW06033K01FKEA")
        (field (name "VALUEMANUFACTURERPARTNUMBER") "Res, SMD, 3.01k, ±1%, 0603, 0.1W")
      )
      (libsource (lib "Resistor") (part "Resistor_0603"))
    )
    (comp (ref "R37")
      (value "~")
      (footprint "PCB_MPPT:RES: 0603")
      (fields
        (field (name "MANUFACTURER") "Vishay")
        (field (name "PARTNUMBER") "CRCW06030000Z0EA")
        (field (name "VALUEMANUFACTURERPARTNUMBER") "Res, SMD, 0, ±1%, 0603, 0.1W")
        (field (name "SHOWCOMMENT") "OPT")
      )
      (libsource (lib "") (part "Resistor_0603_1"))
    )
    (comp (ref "R38")
      (value "10k")
      (footprint "PCB_MPPT:RES: 0603")
      (fields
        (field (name "MANUFACTURER") "Vishay")
        (field (name "PARTNUMBER") "CRCW060310K0JNEAC")
        (field (name "VALUEMANUFACTURERPARTNUMBER") "Res, SMD, 10k, ±5%, 0603, 0.1W")
      )
      (libsource (lib "") (part "Resistor_0603_3"))
    )
    (comp (ref "R39")
      (value "10k")
      (footprint "PCB_MPPT:RES: 0603")
      (fields
        (field (name "MANUFACTURER") "Vishay")
        (field (name "PARTNUMBER") "CRCW060310K0JNEAC")
        (field (name "VALUEMANUFACTURERPARTNUMBER") "Res, SMD, 10k, ±5%, 0603, 0.1W")
      )
      (libsource (lib "Resistor") (part "Resistor_0603"))
    )
    (comp (ref "R40")
      (value "0")
      (footprint "PCB_MPPT:RES: 0603")
      (fields
        (field (name "MANUFACTURER") "Vishay")
        (field (name "PARTNUMBER") "CRCW06030000Z0EA")
        (field (name "VALUEMANUFACTURERPARTNUMBER") "Res, SMD, 0, ±1%, 0603, 0.1W")
      )
      (libsource (lib "Resistor") (part "Resistor_0603"))
    )
    (comp (ref "R41")
      (value "365k")
      (footprint "PCB_MPPT:RES: 0603")
      (fields
        (field (name "MANUFACTURER") "YAGEO")
        (field (name "PARTNUMBER") "RC0603FR-07365KL")
        (field (name "VALUEMANUFACTURERPARTNUMBER") "Res, SMD, 365k, ±1%, 0603, 0.1W")
      )
      (libsource (lib "Resistor") (part "Resistor_0603"))
    )
    (comp (ref "R42")
      (value "53.6k")
      (footprint "PCB_MPPT:RES: 0603")
      (fields
        (field (name "MANUFACTURER") "Vishay")
        (field (name "PARTNUMBER") "CRCW060353K6FKEA")
        (field (name "VALUEMANUFACTURERPARTNUMBER") "Res, SMD, 53.6k, ±1%, 0603, 0.1W")
      )
      (libsource (lib "Resistor") (part "Resistor_0603"))
    )
    (comp (ref "R43")
      (value "0")
      (footprint "PCB_MPPT:RES: 0603")
      (fields
        (field (name "MANUFACTURER") "Vishay")
        (field (name "PARTNUMBER") "CRCW06030000Z0EA")
        (field (name "VALUEMANUFACTURERPARTNUMBER") "Res, SMD, 0, ±1%, 0603, 0.1W")
      )
      (libsource (lib "Resistor") (part "Resistor_0603"))
    )
    (comp (ref "R44")
      (value "25.5k")
      (footprint "PCB_MPPT:RES: 0603")
      (fields
        (field (name "MANUFACTURER") "Vishay")
        (field (name "PARTNUMBER") "CRCW060325K5FKEA")
        (field (name "VALUEMANUFACTURERPARTNUMBER") "Res, SMD, 25.5k, ±1%, 0603, 0.1W")
      )
      (libsource (lib "Resistor") (part "Resistor_0603"))
    )
    (comp (ref "R45")
      (value "~")
      (footprint "PCB_MPPT:RES: 0603")
      (fields
        (field (name "MANUFACTURER") "Vishay")
        (field (name "PARTNUMBER") "CRCW06030000Z0EA")
        (field (name "VALUEMANUFACTURERPARTNUMBER") "Res, SMD, 0, ±1%, 0603, 0.1W")
        (field (name "SHOWCOMMENT") "OPT")
      )
      (libsource (lib "") (part "Resistor_0603_3"))
    )
    (comp (ref "R46")
      (value "11.5k")
      (footprint "PCB_MPPT:RES: 0603")
      (fields
        (field (name "MANUFACTURER") "Vishay")
        (field (name "PARTNUMBER") "CRCW060311K5FKEA")
        (field (name "VALUEMANUFACTURERPARTNUMBER") "Res, SMD, 11.5k, ±1%, 0603, 0.1W")
      )
      (libsource (lib "Resistor") (part "Resistor_0603"))
    )
    (comp (ref "R47")
      (value "4.99k")
      (footprint "PCB_MPPT:RES: 0603")
      (fields
        (field (name "MANUFACTURER") "Vishay")
        (field (name "PARTNUMBER") "CRCW06034K99FKEAC")
        (field (name "VALUEMANUFACTURERPARTNUMBER") "Res, SMD, 4.99k, ±1%, 0603, 0.1W")
      )
      (libsource (lib "Resistor") (part "Resistor_0603"))
    )
    (comp (ref "R48")
      (value "110k")
      (footprint "PCB_MPPT:RES: 0603")
      (fields
        (field (name "MANUFACTURER") "Vishay")
        (field (name "PARTNUMBER") "CRCW0603110KFKEA")
        (field (name "VALUEMANUFACTURERPARTNUMBER") "Res, SMD, 110k, ±1%, 0603, 0.1W")
      )
      (libsource (lib "Resistor") (part "Resistor_0603"))
    )
    (comp (ref "R49")
      (value "10k")
      (footprint "PCB_MPPT:RES: 0603")
      (fields
        (field (name "MANUFACTURER") "Vishay")
        (field (name "PARTNUMBER") "CRCW060310K0JNEAC")
        (field (name "VALUEMANUFACTURERPARTNUMBER") "Res, SMD, 10k, ±5%, 0603, 0.1W")
      )
      (libsource (lib "Resistor") (part "Resistor_0603"))
    )
    (comp (ref "R50")
      (value "100k")
      (footprint "PCB_MPPT:RES: 0603")
      (fields
        (field (name "MANUFACTURER") "Vishay")
        (field (name "PARTNUMBER") "CRCW0603100KFKEA")
        (field (name "VALUEMANUFACTURERPARTNUMBER") "Res, SMD, 100k, ±1%, 0603, 0.1W")
      )
      (libsource (lib "Resistor") (part "Resistor_0603"))
    )
    (comp (ref "R51")
      (value "35.7k")
      (footprint "PCB_MPPT:RES: 0603")
      (fields
        (field (name "MANUFACTURER") "Vishay")
        (field (name "PARTNUMBER") "CRCW060335K7FKEA")
        (field (name "VALUEMANUFACTURERPARTNUMBER") "Res, SMD, 35.7k, ±1%, 0603, 0.1W")
      )
      (libsource (lib "Resistor") (part "Resistor_0603"))
    )
    (comp (ref "R52")
      (value "33.2k")
      (footprint "PCB_MPPT:RES: 0603")
      (fields
        (field (name "MANUFACTURER") "Vishay")
        (field (name "PARTNUMBER") "CRCW060333K2FKEAC")
        (field (name "VALUEMANUFACTURERPARTNUMBER") "Res, SMD, 33.2k, ±1%, 0603, 0.1W")
      )
      (libsource (lib "Resistor") (part "Resistor_0603"))
    )
    (comp (ref "R53")
      (value "1k")
      (footprint "PCB_MPPT:RES: 0603")
      (fields
        (field (name "MANUFACTURER") "Vishay")
        (field (name "PARTNUMBER") "CRCW06031K00FKEA")
        (field (name "VALUEMANUFACTURERPARTNUMBER") "Res, SMD, 1k, ±1%, 0603, 0.1W")
      )
      (libsource (lib "") (part "Resistor_0603_1"))
    )
    (comp (ref "R54")
      (value "0")
      (footprint "PCB_MPPT:RES: 0603")
      (fields
        (field (name "MANUFACTURER") "Vishay")
        (field (name "PARTNUMBER") "CRCW06030000Z0EA")
        (field (name "VALUEMANUFACTURERPARTNUMBER") "Res, SMD, 0, ±1%, 0603, 0.1W")
      )
      (libsource (lib "") (part "Resistor_0603_3"))
    )
    (comp (ref "R55")
      (value "4.7k")
      (footprint "PCB_MPPT:RES: 0805")
      (fields
        (field (name "MANUFACTURER") "TDK")
        (field (name "PARTNUMBER") "B57401V2472J062")
        (field (name "VALUEMANUFACTURERPARTNUMBER") "NTC resistor, 4.7k, ±5%, 0805, 3650K, -55...+125°C")
        (field (name "TOLERANCE") "±5%")
      )
      (libsource (lib "Resistor") (part "NTC"))
    )
    (comp (ref "R56")
      (value "28k")
      (footprint "PCB_MPPT:RES: 0603")
      (fields
        (field (name "MANUFACTURER") "Vishay")
        (field (name "PARTNUMBER") "CRCW060328K0FKEAHP")
        (field (name "VALUEMANUFACTURERPARTNUMBER") "Res, SMD, 28k, ±1%, 0603, 0.1W")
      )
      (libsource (lib "Resistor") (part "Resistor_0603"))
    )
    (comp (ref "R57")
      (value "330")
      (footprint "PCB_MPPT:RES: 0603")
      (fields
        (field (name "MANUFACTURER") "Vishay")
        (field (name "PARTNUMBER") "CRCW0603330RFKEAC")
        (field (name "VALUEMANUFACTURERPARTNUMBER") "Res, SMD, 330, ±1%, 0603, 0.1W")
      )
      (libsource (lib "Resistor") (part "Resistor_0603"))
    )
    (comp (ref "R58")
      (value "5.1k")
      (footprint "PCB_MPPT:RES: 0805")
      (fields
        (field (name "MANUFACTURER") "Vishay")
        (field (name "PARTNUMBER") "CRCW08055K10FKEA")
        (field (name "VALUEMANUFACTURERPARTNUMBER") "Resistor film, 5.1k, ±1%, 0805, 0.125W")
      )
      (libsource (lib "Resistor") (part "Resistor_0805"))
    )
    (comp (ref "R59")
      (value "8.45k")
      (footprint "PCB_MPPT:RES: 0603")
      (fields
        (field (name "MANUFACTURER") "Vishay")
        (field (name "PARTNUMBER") "CRCW06038K45FKEA")
        (field (name "VALUEMANUFACTURERPARTNUMBER") "Res, SMD, 8.45k, ±1%, 0603, 0.1W")
      )
      (libsource (lib "Resistor") (part "Resistor_0603"))
    )
    (comp (ref "SB3")
      (value "~")
      (footprint "PCB_MPPT:BUT: 6x6 SMD")
      (fields
        (field (name "MANUFACTURER") "TE Connectivity")
        (field (name "VALUEMANUFACTURERPARTNUMBER") "Tactile button, 6x6mm")
        (field (name "PARTNUMBER") "FSM2JSMAATR")
        (field (name "COMMENTTEXT") "\"SHDN\"")
      )
      (libsource (lib "Electromechanics") (part "Button_tactile"))
    )
    (comp (ref "VD1")
      (value "~")
      (footprint "PCB_MPPT:PG-TDSON-8-7")
      (fields
        (field (name "MANUFACTURER") "ON Semiconductor")
        (field (name "VALUEMANUFACTURERPARTNUMBER") "Schottky diode, 100V, 10A, 690mV @ 10A, 8-PowerTDFN, 5 Leads")
        (field (name "VOLTAGE") "100V")
        (field (name "PARTNUMBER") "NTS10100MFST3G")
      )
      (libsource (lib "Diode") (part "Schottky_single_TDFN"))
    )
    (comp (ref "VD2")
      (value "~")
      (footprint "PCB_MPPT:DIODE: SMA")
      (fields
        (field (name "MANUFACTURER") "Diodes Incorporated")
        (field (name "VALUEMANUFACTURERPARTNUMBER") "TVS DIODE UNI, 48V, 400W, SMA")
        (field (name "VOLTAGE") "48V")
        (field (name "PARTNUMBER") "SMAJ48A-13-F")
      )
      (libsource (lib "Diode") (part "TVS_single_uni"))
    )
    (comp (ref "VD3")
      (value "~")
      (footprint "PCB_MPPT:DIODE: SOD123F")
      (fields
        (field (name "MANUFACTURER") "Central Semi.")
        (field (name "VALUEMANUFACTURERPARTNUMBER") "Ultra Fast Rectifier Single, 200V, 1A, SOD-123F")
        (field (name "VOLTAGE") "200V")
        (field (name "PARTNUMBER") "CMMR1U-02 TR")
      )
      (libsource (lib "Diode") (part "Diode_single"))
    )
    (comp (ref "VD4")
      (value "~")
      (footprint "PCB_MPPT:DIODE: SOD123F")
      (fields
        (field (name "MANUFACTURER") "Central Semi.")
        (field (name "VALUEMANUFACTURERPARTNUMBER") "Ultra Fast Rectifier Single, 200V, 1A, SOD-123F")
        (field (name "VOLTAGE") "200V")
        (field (name "PARTNUMBER") "CMMR1U-02 TR")
      )
      (libsource (lib "Diode") (part "Diode_single"))
    )
    (comp (ref "VD5")
      (value "~")
      (footprint "PCB_MPPT:LED: 0603G")
      (fields
        (field (name "MANUFACTURER") "Wurth")
        (field (name "VALUEMANUFACTURERPARTNUMBER") "LED, 0603, GREEN")
        (field (name "PARTNUMBER") "150060VS75000")
        (field (name "COLOR") "GREEN")
        (field (name "SHOWCOMMENT") "STATUS")
      )
      (libsource (lib "Diode") (part "LED_single"))
    )
    (comp (ref "VD6")
      (value "~")
      (footprint "PCB_MPPT:DIODE: SOD523")
      (fields
        (field (name "MANUFACTURER") "Diodes Incorporated")
        (field (name "VALUEMANUFACTURERPARTNUMBER") "Zener diode, 12V, 300mW, SOD-523")
        (field (name "VOLTAGE") "12V")
        (field (name "PARTNUMBER") "BZT52C12T-7")
      )
      (libsource (lib "Diode") (part "Zener_single"))
    )
    (comp (ref "VD7")
      (value "~")
      (footprint "PCB_MPPT:DIODE: SMA")
      (fields
        (field (name "MANUFACTURER") "Diodes Incorporated")
        (field (name "VALUEMANUFACTURERPARTNUMBER") "TVS DIODE UNI, 70V, 400W, SMA")
        (field (name "VOLTAGE") "70V")
        (field (name "PARTNUMBER") "SMAT70A-13-F")
      )
      (libsource (lib "Diode") (part "TVS_single_uni"))
    )
    (comp (ref "VD8")
      (value "~")
      (footprint "PCB_MPPT:DIODE: SMA")
      (fields
        (field (name "MANUFACTURER") "Diodes Incorporated")
        (field (name "VALUEMANUFACTURERPARTNUMBER") "TVS DIODE UNI, 24V, 400W, SMA")
        (field (name "VOLTAGE") "24V")
        (field (name "PARTNUMBER") "SMAJ24A-13-F")
      )
      (libsource (lib "Diode") (part "TVS_single_uni"))
    )
    (comp (ref "VD9")
      (value "~")
      (footprint "PCB_MPPT:LED: 0603G")
      (fields
        (field (name "MANUFACTURER") "Wurth")
        (field (name "VALUEMANUFACTURERPARTNUMBER") "LED, 0603, GREEN")
        (field (name "PARTNUMBER") "150060VS75000")
        (field (name "COLOR") "GREEN")
        (field (name "SHOWCOMMENT") "3V3")
      )
      (libsource (lib "Diode") (part "LED_single"))
    )
    (comp (ref "VD10")
      (value "~")
      (footprint "PCB_MPPT:DIODE: SMA")
      (fields
        (field (name "MANUFACTURER") "Vishay")
        (field (name "VALUEMANUFACTURERPARTNUMBER") "Schottky diode, 100V, 1A, , SMA")
        (field (name "VOLTAGE") "100V")
        (field (name "PARTNUMBER") "MBR0580S1-7")
      )
      (libsource (lib "Diode") (part "Schottky_single"))
    )
    (comp (ref "VD19")
      (value "~")
      (footprint "PCB_MPPT:DIODE: SMA")
      (fields
        (field (name "MANUFACTURER") "Vishay")
        (field (name "VALUEMANUFACTURERPARTNUMBER") "Schottky diode, 100V, 1A, , SMA")
        (field (name "VOLTAGE") "100V")
        (field (name "PARTNUMBER") "MBR0580S1-7")
      )
      (libsource (lib "Diode") (part "Schottky_single"))
    )
    (comp (ref "VD20")
      (value "~")
      (footprint "PCB_MPPT:DIODE: SMA")
      (fields
        (field (name "MANUFACTURER") "Vishay")
        (field (name "VALUEMANUFACTURERPARTNUMBER") "Schottky diode, 100V, 1A, , SMA")
        (field (name "VOLTAGE") "100V")
        (field (name "PARTNUMBER") "MBR0580S1-7")
      )
      (libsource (lib "Diode") (part "Schottky_single"))
    )
    (comp (ref "VT1")
      (value "MOSFET N-ch, 150V, PG-TDSON-8")
      (footprint "PCB_MPPT:PG-TDSON-8-7")
      (description "Транзистор")
      (fields
        (field (name "MANUFACTURER") "Infineon Technologies")
        (field (name "PARTNUMBER") "BSC110N15NS5")
      )
      (libsource (lib "Transistor") (part "MOSFET_N_TDSON-8"))
    )
    (comp (ref "VT2")
      (value "MOSFET N-ch, 150V, PG-TDSON-8")
      (footprint "PCB_MPPT:PG-TDSON-8-7")
      (description "Транзистор")
      (fields
        (field (name "MANUFACTURER") "Infineon Technologies")
        (field (name "PARTNUMBER") "BSC110N15NS5")
      )
      (libsource (lib "Transistor") (part "MOSFET_N_TDSON-8"))
    )
    (comp (ref "VT3")
      (value "MOSFET N-ch, 150V, PG-TDSON-8")
      (footprint "PCB_MPPT:PG-TDSON-8-7")
      (description "Транзистор")
      (fields
        (field (name "MANUFACTURER") "Infineon Technologies")
        (field (name "PARTNUMBER") "BSC110N15NS5")
      )
      (libsource (lib "Transistor") (part "MOSFET_N_TDSON-8"))
    )
    (comp (ref "VT4")
      (value "MOSFET N-ch, 150V, PG-TDSON-8")
      (footprint "PCB_MPPT:PG-TDSON-8-7")
      (description "Транзистор")
      (fields
        (field (name "MANUFACTURER") "Infineon Technologies")
        (field (name "PARTNUMBER") "BSC110N15NS5")
      )
      (libsource (lib "Transistor") (part "MOSFET_N_TDSON-8"))
    )
    (comp (ref "VT5")
      (value "~")
      (footprint "PCB_MPPT:SOT23")
      (fields
        (field (name "MANUFACTURER") "Diodes Inc.")
        (field (name "VALUEMANUFACTURERPARTNUMBER") "NPN transistor, 40V, 200mA, SOT-23")
        (field (name "PARTNUMBER") "MMBT3904-7-F")
      )
      (libsource (lib "Transistor") (part "BJT_NPN_132"))
    )
    (comp (ref "VT6")
      (value "~")
      (footprint "PCB_MPPT:PG-TDSON-8-7")
      (description "Транзистор")
      (fields
        (field (name "MANUFACTURER") "ON Semiconductor")
        (field (name "VALUEMANUFACTURERPARTNUMBER") "MOSFET N-ch, 100V, 12A, 8-PowerTDFN")
        (field (name "PARTNUMBER") "FDMS86101")
      )
      (libsource (lib "Transistor") (part "MOSFET_N_TDSON-8"))
    )
    (comp (ref "XP1")
      (value "PV+")
      (footprint "PCB_MPPT:CON: Keystone5000")
      (description "Test Point, Miniature, Red, TH")
      (fields (field (name "PARTNUMBER") "5000") (field (name "MANUFACTURER") "Keystone"))
      (libsource (lib "Connector") (part "5000"))
    )
    (comp (ref "XP2")
      (value "VBAT")
      (footprint "PCB_MPPT:CON: Keystone5000")
      (description "Test Point, Miniature, Red, TH")
      (fields (field (name "PARTNUMBER") "5000") (field (name "MANUFACTURER") "Keystone"))
      (libsource (lib "Connector") (part "5000"))
    )
    (comp (ref "XP3")
      (value "DC+")
      (footprint "PCB_MPPT:CON: Keystone5000")
      (description "Test Point, Miniature, Red, TH")
      (fields (field (name "PARTNUMBER") "5000") (field (name "MANUFACTURER") "Keystone"))
      (libsource (lib "Connector") (part "5000"))
    )
    (comp (ref "XP4")
      (value "AGND")
      (footprint "PCB_MPPT:CON: Keystone5001")
      (description "Test Point, Miniature, Black, TH")
      (fields
        (field (name "PARTNUMBER") "5001")
        (field (name "VALUEMANUFACTURERPARTNUMBER") "Test Point, Black")
      )
      (libsource (lib "Connector") (part "5001"))
    )
    (comp (ref "XP5")
      (value "GND")
      (footprint "PCB_MPPT:CON: Keystone5001")
      (description "Test Point, Miniature, Black, TH")
      (fields
        (field (name "PARTNUMBER") "5001")
        (field (name "VALUEMANUFACTURERPARTNUMBER") "Test Point, Black")
      )
      (libsource (lib "Connector") (part "5001"))
    )
    (comp (ref "XP6")
      (value "3V3")
      (footprint "PCB_MPPT:CON: Keystone5000")
      (description "Test Point, Miniature, Red, TH")
      (fields (field (name "PARTNUMBER") "5000") (field (name "MANUFACTURER") "Keystone"))
      (libsource (lib "Connector") (part "5000"))
    )
    (comp (ref "XP10")
      (value "AGND")
      (footprint "PCB_MPPT:CON: Keystone5001")
      (description "Test Point, Miniature, Black, TH")
      (fields
        (field (name "PARTNUMBER") "5001")
        (field (name "VALUEMANUFACTURERPARTNUMBER") "Test Point, Black")
      )
      (libsource (lib "Connector") (part "5001"))
    )
    (comp (ref "XT1")
      (value "~")
      (footprint "PCB_MPPT:CON: 6PCV-02-006")
      (fields
        (field (name "MANUFACTURER") "TE Connectivity")
        (field (name "VALUEMANUFACTURERPARTNUMBER") "Connector, 2pin, 9.53mm, 300VAC, 25A")
        (field (name "PARTNUMBER") "6PCV-02-006")
        (field (name "COMMENTTEXT") "\"PANEL IN\"")
        (field (name "ROW1") "PV+")
        (field (name "ROW2") "PV-")
      )
      (libsource (lib "") (part "Connector_6PCV-02_1"))
    )
    (comp (ref "XT2")
      (value "~")
      (footprint "PCB_MPPT:CON: 6PCV-02-006")
      (fields
        (field (name "MANUFACTURER") "TE Connectivity")
        (field (name "VALUEMANUFACTURERPARTNUMBER") "Connector, 2pin, 9.53mm, 300VAC, 25A")
        (field (name "PARTNUMBER") "6PCV-02-006")
        (field (name "COMMENTTEXT") "\"VBAT\"")
        (field (name "ROW1") "BAT+")
        (field (name "ROW2") "BAT-")
      )
      (libsource (lib "Connector") (part "Connector_6PCV-02"))
    )
    (comp (ref "XT3")
      (value "~")
      (footprint "CON: DG350-3.5-02P")
      (fields
        (field (name "MANUFACTURER") "Molex")
        (field (name "VALUEMANUFACTURERPARTNUMBER") "Terminal connector, 2pin, 3.5mm, 300VAC, 12A")
        (field (name "PARTNUMBER") "0393570002")
        (field (name "COMMENTTEXT") "\"NTC\"")
        (field (name "ROW1") "SENSE+")
        (field (name "ROW2") "SENSE-")
      )
      (libsource (lib "") (part "Connector_terminal_2pin_1"))
    )
    (comp (ref "XT4")
      (value "~")
      (footprint "PCB_MPPT:CON: 6PCV-02-006")
      (fields
        (field (name "MANUFACTURER") "TE Connectivity")
        (field (name "VALUEMANUFACTURERPARTNUMBER") "Connector, 2pin, 9.53mm, 300VAC, 25A")
        (field (name "PARTNUMBER") "6PCV-02-006")
        (field (name "COMMENTTEXT") "\"DC IN\"")
        (field (name "ROW1") "DC+")
        (field (name "ROW2") "DC-")
      )
      (libsource (lib "") (part "Connector_6PCV-02_1"))
    )
    (comp (ref "XT6")
      (value "~")
      (footprint "CON: DG350-3.5-02P")
      (fields
        (field (name "MANUFACTURER") "Molex")
        (field (name "VALUEMANUFACTURERPARTNUMBER") "Terminal connector, 2pin, 3.5mm, 300VAC, 12A")
        (field (name "PARTNUMBER") "0393570002")
        (field (name "COMMENTTEXT") "\"7-48VIN\"")
        (field (name "ROW1") "VIN")
        (field (name "ROW2") "GND")
      )
      (libsource (lib "Connector") (part "Connector_terminal_2pin"))
    )
  )
  (nets
    (net (code "1") (name "/BG1") (class "Default")
      (node (ref "DA1") (pin "23") (pinfunction "BG1_23") (pintype "passive"))
      (node (ref "R9") (pin "1") (pinfunction "1_1") (pintype "passive"))
    )
    (net (code "2") (name "/BG2") (class "Default")
      (node (ref "DA1") (pin "25") (pinfunction "BG2_25") (pintype "passive"))
      (node (ref "R10") (pin "1") (pinfunction "1_1") (pintype "passive"))
    )
    (net (code "3") (name "/BOOST1") (class "Default")
      (node (ref "C23") (pin "2") (pinfunction "2_2") (pintype "passive"))
      (node (ref "DA1") (pin "33") (pinfunction "BOOST1_33") (pintype "passive"))
      (node (ref "VD4") (pin "2") (pinfunction "2_2") (pintype "passive"))
    )
    (net (code "4") (name "/BOOST2") (class "Default")
      (node (ref "C24") (pin "1") (pinfunction "1_1") (pintype "passive"))
      (node (ref "DA1") (pin "27") (pinfunction "BOOST2_27") (pintype "passive"))
      (node (ref "VD3") (pin "2") (pinfunction "2_2") (pintype "passive"))
    )
    (net (code "5") (name "/CSN") (class "Default")
      (node (ref "C20") (pin "1") (pinfunction "1_1") (pintype "passive"))
      (node (ref "C22") (pin "1") (pinfunction "1_1") (pintype "passive"))
      (node (ref "DA1") (pin "12") (pinfunction "CSN_12") (pintype "passive"))
      (node (ref "R15") (pin "2") (pinfunction "2_2") (pintype "passive"))
    )
    (net (code "6") (name "/CSP") (class "Default")
      (node (ref "C20") (pin "2") (pinfunction "2_2") (pintype "passive"))
      (node (ref "C21") (pin "1") (pinfunction "1_1") (pintype "passive"))
      (node (ref "DA1") (pin "13") (pinfunction "CSP_13") (pintype "passive"))
      (node (ref "R14") (pin "2") (pinfunction "2_2") (pintype "passive"))
    )
    (net (code "7") (name "/DC_IN") (class "Default")
      (node (ref "DA2") (pin "3") (pinfunction "SOURCE_3") (pintype "passive"))
      (node (ref "DA2") (pin "4") (pinfunction "IN_4") (pintype "passive"))
      (node (ref "R50") (pin "2") (pinfunction "2_2") (pintype "passive"))
      (node (ref "VD6") (pin "1") (pinfunction "A_1") (pintype "passive"))
      (node (ref "VD7") (pin "2") (pinfunction "C_2") (pintype "passive"))
      (node (ref "VT6") (pin "1") (pinfunction "S_1") (pintype "passive"))
      (node (ref "VT6") (pin "2") (pinfunction "S_2") (pintype "passive"))
      (node (ref "VT6") (pin "3") (pinfunction "S_3") (pintype "passive"))
      (node (ref "XP3") (pin "1") (pintype "passive"))
      (node (ref "XT4") (pin "1") (pinfunction "1_1") (pintype "passive"))
    )
    (net (code "8") (name "/EXTVCC") (class "Default")
      (node (ref "C28") (pin "1") (pinfunction "1_1") (pintype "passive"))
      (node (ref "DA1") (pin "40") (pinfunction "EXTVCC_40") (pintype "passive"))
      (node (ref "R3") (pin "2") (pinfunction "2_2") (pintype "passive"))
    )
    (net (code "9") (name "/GATEVCC") (class "Default")
      (node (ref "8") (pin "1") (pinfunction "1_1") (pintype "passive"))
      (node (ref "C29") (pin "2") (pinfunction "2_2") (pintype "passive"))
      (node (ref "C30") (pin "1") (pinfunction "1_1") (pintype "passive"))
      (node (ref "DA1") (pin "24") (pinfunction "GATEVCC_24") (pintype "passive"))
      (node (ref "DA1") (pin "7") (pinfunction "INTVCC_7") (pintype "passive"))
      (node (ref "R13") (pin "2") (pinfunction "2_2") (pintype "passive"))
      (node (ref "R45") (pin "2") (pinfunction "2_2") (pintype "passive"))
    )
    (net (code "10") (name "/SCL") (class "Default")
      (node (ref "14") (pin "1") (pinfunction "1_1") (pintype "passive"))
      (node (ref "DA1") (pin "63") (pinfunction "SCL_63") (pintype "passive"))
      (node (ref "R35") (pin "2") (pinfunction "2_2") (pintype "passive"))
    )
    (net (code "11") (name "/SDA") (class "Default")
      (node (ref "16") (pin "1") (pinfunction "1_1") (pintype "passive"))
      (node (ref "DA1") (pin "61") (pinfunction "SDA_61") (pintype "passive"))
      (node (ref "R38") (pin "2") (pinfunction "2_2") (pintype "passive"))
    )
    (net (code "12") (name "/SW1") (class "Default")
      (node (ref "C23") (pin "1") (pinfunction "1_1") (pintype "passive"))
      (node (ref "DA1") (pin "31") (pinfunction "SW1_31") (pintype "passive"))
      (node (ref "L1") (pin "2") (pinfunction "2_2") (pintype "passive"))
      (node (ref "R6") (pin "2") (pinfunction "2_2") (pintype "passive"))
      (node (ref "VT1") (pin "1") (pinfunction "S_1") (pintype "passive"))
      (node (ref "VT1") (pin "2") (pinfunction "S_2") (pintype "passive"))
      (node (ref "VT1") (pin "3") (pinfunction "S_3") (pintype "passive"))
      (node (ref "VT3") (pin "5") (pinfunction "D_5") (pintype "passive"))
      (node (ref "VT3") (pin "6") (pinfunction "D_6") (pintype "passive"))
      (node (ref "VT3") (pin "7") (pinfunction "D_7") (pintype "passive"))
      (node (ref "VT3") (pin "8") (pinfunction "D_8") (pintype "passive"))
    )
    (net (code "13") (name "/SW2") (class "Default")
      (node (ref "C24") (pin "2") (pinfunction "2_2") (pintype "passive"))
      (node (ref "DA1") (pin "29") (pinfunction "SW2_29") (pintype "passive"))
      (node (ref "L1") (pin "1") (pinfunction "1_1") (pintype "passive"))
      (node (ref "R7") (pin "2") (pinfunction "2_2") (pintype "passive"))
      (node (ref "VT2") (pin "1") (pinfunction "S_1") (pintype "passive"))
      (node (ref "VT2") (pin "2") (pinfunction "S_2") (pintype "passive"))
      (node (ref "VT2") (pin "3") (pinfunction "S_3") (pintype "passive"))
      (node (ref "VT4") (pin "5") (pinfunction "D_5") (pintype "passive"))
      (node (ref "VT4") (pin "6") (pinfunction "D_6") (pintype "passive"))
      (node (ref "VT4") (pin "7") (pinfunction "D_7") (pintype "passive"))
      (node (ref "VT4") (pin "8") (pinfunction "D_8") (pintype "passive"))
    )
    (net (code "14") (name "/TEMP") (class "Default")
      (node (ref "18") (pin "1") (pinfunction "1_1") (pintype "passive"))
      (node (ref "C46") (pin "2") (pinfunction "2_2") (pintype "passive"))
      (node (ref "R55") (pin "1") (pinfunction "1_1") (pintype "passive"))
      (node (ref "R58") (pin "1") (pinfunction "1_1") (pintype "passive"))
    )
    (net (code "15") (name "/TG1") (class "Default")
      (node (ref "DA1") (pin "32") (pinfunction "TG1_32") (pintype "passive"))
      (node (ref "R8") (pin "1") (pinfunction "1_1") (pintype "passive"))
    )
    (net (code "16") (name "/TG2") (class "Default")
      (node (ref "DA1") (pin "28") (pinfunction "TG2_28") (pintype "passive"))
      (node (ref "R11") (pin "1") (pinfunction "1_1") (pintype "passive"))
    )
    (net (code "17") (name "/VBATF") (class "Default")
      (node (ref "FU1") (pin "2") (pinfunction "2_2") (pintype "passive"))
      (node (ref "XT2") (pin "1") (pinfunction "1_1") (pintype "passive"))
    )
    (net (code "18") (name "/VINR") (class "Default")
      (node (ref "6") (pin "1") (pinfunction "1_1") (pintype "passive"))
      (node (ref "DA1") (pin "54") (pinfunction "VINR_54") (pintype "passive"))
      (node (ref "R19") (pin "2") (pinfunction "2_2") (pintype "passive"))
      (node (ref "R28") (pin "1") (pinfunction "1_1") (pintype "passive"))
      (node (ref "VT5") (pin "3") (pinfunction "C_3") (pintype "passive"))
    )
    (net (code "19") (name "/VIN_MCU") (class "Default")
      (node (ref "JP4") (pin "2") (pinfunction "2_2") (pintype "passive"))
      (node (ref "VD19") (pin "1") (pinfunction "1_1") (pintype "passive"))
    )
    (net (code "20") (name "3.3V") (class "Default")
      (node (ref "R54") (pin "1") (pinfunction "1_1") (pintype "passive"))
      (node (ref "R55") (pin "2") (pinfunction "2_2") (pintype "passive"))
      (node (ref "VD9") (pin "1") (pinfunction "A_1") (pintype "passive"))
      (node (ref "XP6") (pin "1") (pintype "passive"))
    )
    (net (code "21") (name "A") (class "Default")
      (node (ref "C18") (pin "1") (pinfunction "1_1") (pintype "passive"))
      (node (ref "C19") (pin "1") (pinfunction "1_1") (pintype "passive"))
      (node (ref "R12") (pin "2") (pinfunction "2_2") (pintype "passive"))
      (node (ref "R14") (pin "1") (pinfunction "1_1") (pintype "passive"))
      (node (ref "VT3") (pin "1") (pinfunction "S_1") (pintype "passive"))
      (node (ref "VT3") (pin "2") (pinfunction "S_2") (pintype "passive"))
      (node (ref "VT3") (pin "3") (pinfunction "S_3") (pintype "passive"))
      (node (ref "VT4") (pin "1") (pinfunction "S_1") (pintype "passive"))
      (node (ref "VT4") (pin "2") (pinfunction "S_2") (pintype "passive"))
      (node (ref "VT4") (pin "3") (pinfunction "S_3") (pintype "passive"))
    )
    (net (code "22") (name "AGND") (class "Default")
      (node (ref "C14") (pin "1") (pinfunction "1_1") (pintype "passive"))
      (node (ref "C17") (pin "1") (pinfunction "1_1") (pintype "passive"))
      (node (ref "C21") (pin "2") (pinfunction "2_2") (pintype "passive"))
      (node (ref "C22") (pin "2") (pinfunction "2_2") (pintype "passive"))
      (node (ref "C25") (pin "1") (pinfunction "1_1") (pintype "passive"))
      (node (ref "C26") (pin "1") (pinfunction "1_1") (pintype "passive"))
      (node (ref "C27") (pin "1") (pinfunction "1_1") (pintype "passive"))
      (node (ref "C28") (pin "2") (pinfunction "2_2") (pintype "passive"))
      (node (ref "C29") (pin "1") (pinfunction "1_1") (pintype "passive"))
      (node (ref "C30") (pin "2") (pinfunction "2_2") (pintype "passive"))
      (node (ref "C31") (pin "1") (pinfunction "1_1") (pintype "passive"))
      (node (ref "C32") (pin "1") (pinfunction "1_1") (pintype "passive"))
      (node (ref "C33") (pin "1") (pinfunction "1_1") (pintype "passive"))
      (node (ref "C34") (pin "1") (pinfunction "1_1") (pintype "passive"))
      (node (ref "C35") (pin "1") (pinfunction "1_1") (pintype "passive"))
      (node (ref "C36") (pin "1") (pinfunction "1_1") (pintype "passive"))
      (node (ref "C37") (pin "1") (pinfunction "1_1") (pintype "passive"))
      (node (ref "C38") (pin "1") (pinfunction "1_1") (pintype "passive"))
      (node (ref "C39") (pin "1") (pinfunction "1_1") (pintype "passive"))
      (node (ref "C42") (pin "1") (pinfunction "1_1") (pintype "passive"))
      (node (ref "C43") (pin "1") (pinfunction "1_1") (pintype "passive"))
      (node (ref "C44") (pin "1") (pinfunction "1_1") (pintype "passive"))
      (node (ref "C45") (pin "1") (pinfunction "1_1") (pintype "passive"))
      (node (ref "C46") (pin "1") (pinfunction "1_1") (pintype "passive"))
      (node (ref "DA1") (pin "52") (pinfunction "NC_52") (pintype "passive"))
      (node (ref "DA1") (pin "55") (pinfunction "GND_55") (pintype "passive"))
      (node (ref "DA1") (pin "59") (pinfunction "GND_59") (pintype "passive"))
      (node (ref "DA1") (pin "60") (pinfunction "NC_60") (pintype "passive"))
      (node (ref "DA1") (pin "62") (pinfunction "GND_62") (pintype "passive"))
      (node (ref "DA1") (pin "65") (pinfunction "EP_65") (pintype "passive"))
      (node (ref "DA3") (pin "2") (pinfunction "GND_2") (pintype "power_in"))
      (node (ref "NT1") (pin "1") (pinfunction "1_1") (pintype "passive"))
      (node (ref "R26") (pin "2") (pinfunction "2_2") (pintype "passive"))
      (node (ref "R27") (pin "1") (pinfunction "1_1") (pintype "passive"))
      (node (ref "R28") (pin "2") (pinfunction "2_2") (pintype "passive"))
      (node (ref "R29") (pin "2") (pinfunction "2_2") (pintype "passive"))
      (node (ref "R33") (pin "1") (pinfunction "1_1") (pintype "passive"))
      (node (ref "R34") (pin "1") (pinfunction "1_1") (pintype "passive"))
      (node (ref "R39") (pin "1") (pinfunction "1_1") (pintype "passive"))
      (node (ref "R40") (pin "1") (pinfunction "1_1") (pintype "passive"))
      (node (ref "R41") (pin "1") (pinfunction "1_1") (pintype "passive"))
      (node (ref "R44") (pin "1") (pinfunction "1_1") (pintype "passive"))
      (node (ref "R45") (pin "1") (pinfunction "1_1") (pintype "passive"))
      (node (ref "R49") (pin "1") (pinfunction "1_1") (pintype "passive"))
      (node (ref "R51") (pin "1") (pinfunction "1_1") (pintype "passive"))
      (node (ref "R57") (pin "1") (pinfunction "1_1") (pintype "passive"))
      (node (ref "R58") (pin "2") (pinfunction "2_2") (pintype "passive"))
      (node (ref "R59") (pin "1") (pinfunction "1_1") (pintype "passive"))
      (node (ref "SB3") (pin "1") (pinfunction "1_1") (pintype "passive"))
      (node (ref "VD10") (pin "1") (pinfunction "1_1") (pintype "passive"))
      (node (ref "VT5") (pin "2") (pinfunction "E_2") (pintype "passive"))
      (node (ref "XP10") (pin "1") (pintype "passive"))
      (node (ref "XP4") (pin "1") (pintype "passive"))
      (node (ref "XT3") (pin "2") (pinfunction "2_2") (pintype "passive"))
      (node (ref "XT6") (pin "2") (pinfunction "2_2") (pintype "passive"))
    )
    (net (code "23") (name "AVDD") (class "Default")
      (node (ref "C32") (pin "2") (pinfunction "2_2") (pintype "passive"))
      (node (ref "DA1") (pin "58") (pinfunction "AVDD_58") (pintype "passive"))
      (node (ref "R32") (pin "2") (pinfunction "2_2") (pintype "passive"))
    )
    (net (code "24") (name "GND") (class "Default")
      (node (ref "C1") (pin "2") (pinfunction "2_2") (pintype "power_in"))
      (node (ref "C11") (pin "1") (pinfunction "1_1") (pintype "passive"))
      (node (ref "C12") (pin "1") (pinfunction "1_1") (pintype "passive"))
      (node (ref "C13") (pin "2") (pinfunction "2_2") (pintype "power_in"))
      (node (ref "C2") (pin "2") (pinfunction "2_2") (pintype "power_in"))
      (node (ref "C3") (pin "2") (pinfunction "2_2") (pintype "power_in"))
      (node (ref "C4") (pin "1") (pinfunction "1_1") (pintype "passive"))
      (node (ref "C5") (pin "1") (pinfunction "1_1") (pintype "passive"))
      (node (ref "C6") (pin "1") (pinfunction "1_1") (pintype "passive"))
      (node (ref "C7") (pin "1") (pinfunction "1_1") (pintype "passive"))
      (node (ref "C8") (pin "1") (pinfunction "1_1") (pintype "passive"))
      (node (ref "C9") (pin "1") (pinfunction "1_1") (pintype "passive"))
      (node (ref "NT1") (pin "2") (pinfunction "2_2") (pintype "passive"))
      (node (ref "R12") (pin "1") (pinfunction "1_1") (pintype "passive"))
      (node (ref "R15") (pin "1") (pinfunction "1_1") (pintype "passive"))
      (node (ref "R52") (pin "1") (pinfunction "1_1") (pintype "passive"))
      (node (ref "R53") (pin "2") (pinfunction "2_2") (pintype "passive"))
      (node (ref "VD2") (pin "1") (pinfunction "A_1") (pintype "passive"))
      (node (ref "XP5") (pin "1") (pintype "passive"))
      (node (ref "XT1") (pin "2") (pinfunction "2_2") (pintype "passive"))
      (node (ref "XT2") (pin "2") (pinfunction "2_2") (pintype "passive"))
      (node (ref "XT4") (pin "2") (pinfunction "2_2") (pintype "passive"))
    )
    (net (code "25") (name "Net-(C6-Pad2)") (class "Default")
      (node (ref "C6") (pin "2") (pinfunction "2_2") (pintype "passive"))
      (node (ref "C7") (pin "2") (pinfunction "2_2") (pintype "passive"))
      (node (ref "R1") (pin "1") (pinfunction "1_1") (pintype "passive"))
      (node (ref "R5") (pin "1") (pinfunction "1_1") (pintype "passive"))
      (node (ref "VT1") (pin "5") (pinfunction "D_5") (pintype "passive"))
      (node (ref "VT1") (pin "6") (pinfunction "D_6") (pintype "passive"))
      (node (ref "VT1") (pin "7") (pinfunction "D_7") (pintype "passive"))
      (node (ref "VT1") (pin "8") (pinfunction "D_8") (pintype "passive"))
    )
    (net (code "26") (name "Net-(C11-Pad2)") (class "Default")
      (node (ref "C11") (pin "2") (pinfunction "2_2") (pintype "passive"))
      (node (ref "C12") (pin "2") (pinfunction "2_2") (pintype "passive"))
      (node (ref "C13") (pin "1") (pinfunction "1_1") (pintype "power_in"))
      (node (ref "R2") (pin "1") (pinfunction "1_1") (pintype "passive"))
      (node (ref "R4") (pin "1") (pinfunction "1_1") (pintype "passive"))
      (node (ref "VD1") (pin "1") (pinfunction "A_1") (pintype "passive"))
      (node (ref "VD1") (pin "2") (pinfunction "A_2") (pintype "passive"))
      (node (ref "VD1") (pin "3") (pinfunction "A_3") (pintype "passive"))
    )
    (net (code "27") (name "Net-(C18-Pad2)") (class "Default")
      (node (ref "C18") (pin "2") (pinfunction "2_2") (pintype "passive"))
      (node (ref "R6") (pin "1") (pinfunction "1_1") (pintype "passive"))
    )
    (net (code "28") (name "Net-(C19-Pad2)") (class "Default")
      (node (ref "C19") (pin "2") (pinfunction "2_2") (pintype "passive"))
      (node (ref "R7") (pin "1") (pinfunction "1_1") (pintype "passive"))
    )
    (net (code "29") (name "Net-(C26-Pad2)") (class "Default")
      (node (ref "C26") (pin "2") (pinfunction "2_2") (pintype "passive"))
      (node (ref "R22") (pin "1") (pinfunction "1_1") (pintype "passive"))
      (node (ref "R23") (pin "2") (pinfunction "2_2") (pintype "passive"))
    )
    (net (code "30") (name "Net-(C27-Pad2)") (class "Default")
      (node (ref "C27") (pin "2") (pinfunction "2_2") (pintype "passive"))
      (node (ref "R24") (pin "2") (pinfunction "2_2") (pintype "passive"))
      (node (ref "R25") (pin "1") (pinfunction "1_1") (pintype "passive"))
    )
    (net (code "31") (name "Net-(C36-Pad2)") (class "Default")
      (node (ref "C36") (pin "2") (pinfunction "2_2") (pintype "passive"))
      (node (ref "R42") (pin "1") (pinfunction "1_1") (pintype "passive"))
      (node (ref "R43") (pin "1") (pinfunction "1_1") (pintype "passive"))
    )
    (net (code "32") (name "Net-(C39-Pad2)") (class "Default")
      (node (ref "C39") (pin "2") (pinfunction "2_2") (pintype "passive"))
      (node (ref "R47") (pin "1") (pinfunction "1_1") (pintype "passive"))
    )
    (net (code "33") (name "Net-(C44-Pad2)") (class "Default")
      (node (ref "C44") (pin "2") (pinfunction "2_2") (pintype "passive"))
      (node (ref "C45") (pin "2") (pinfunction "2_2") (pintype "passive"))
      (node (ref "L2") (pin "1") (pinfunction "1_1") (pintype "passive"))
      (node (ref "R54") (pin "2") (pinfunction "2_2") (pintype "passive"))
      (node (ref "R56") (pin "2") (pinfunction "2_2") (pintype "passive"))
    )
    (net (code "34") (name "Net-(DA1-CA)") (class "Default")
      (node (ref "DA1") (pin "2") (pinfunction "CA_2") (pintype "passive"))
      (node (ref "R30") (pin "1") (pinfunction "1_1") (pintype "passive"))
    )
    (net (code "35") (name "Net-(DA1-CLKDET)") (class "Default")
      (node (ref "DA1") (pin "56") (pinfunction "CLKDET_56") (pintype "passive"))
      (node (ref "R43") (pin "2") (pinfunction "2_2") (pintype "passive"))
    )
    (net (code "36") (name "Net-(DA1-CLKOUT)") (class "Default")
      (node (ref "15") (pin "1") (pinfunction "1_1") (pintype "passive"))
      (node (ref "DA1") (pin "20") (pinfunction "CLKOUT_20") (pintype "passive"))
      (node (ref "R42") (pin "2") (pinfunction "2_2") (pintype "passive"))
    )
    (net (code "37") (name "Net-(DA1-CSNIN)") (class "Default")
      (node (ref "2") (pin "1") (pinfunction "1_1") (pintype "passive"))
      (node (ref "C16") (pin "2") (pinfunction "2_2") (pintype "passive"))
      (node (ref "DA1") (pin "44") (pinfunction "CSNIN_44") (pintype "passive"))
      (node (ref "R5") (pin "2") (pinfunction "2_2") (pintype "passive"))
    )
    (net (code "38") (name "Net-(DA1-CSNOUT)") (class "Default")
      (node (ref "4") (pin "1") (pinfunction "1_1") (pintype "passive"))
      (node (ref "C15") (pin "2") (pinfunction "2_2") (pintype "passive"))
      (node (ref "DA1") (pin "41") (pinfunction "CSNOUT_41") (pintype "passive"))
      (node (ref "R4") (pin "2") (pinfunction "2_2") (pintype "passive"))
    )
    (net (code "39") (name "Net-(DA1-CSPOUT)") (class "Default")
      (node (ref "3") (pin "1") (pinfunction "1_1") (pintype "passive"))
      (node (ref "C14") (pin "2") (pinfunction "2_2") (pintype "passive"))
      (node (ref "C15") (pin "1") (pinfunction "1_1") (pintype "passive"))
      (node (ref "C8") (pin "2") (pinfunction "2_2") (pintype "passive"))
      (node (ref "C9") (pin "2") (pinfunction "2_2") (pintype "passive"))
      (node (ref "DA1") (pin "42") (pinfunction "CSPOUT_42") (pintype "passive"))
      (node (ref "R2") (pin "2") (pinfunction "2_2") (pintype "passive"))
      (node (ref "R3") (pin "1") (pinfunction "1_1") (pintype "passive"))
      (node (ref "VT2") (pin "5") (pinfunction "D_5") (pintype "passive"))
      (node (ref "VT2") (pin "6") (pinfunction "D_6") (pintype "passive"))
      (node (ref "VT2") (pin "7") (pinfunction "D_7") (pintype "passive"))
      (node (ref "VT2") (pin "8") (pinfunction "D_8") (pintype "passive"))
    )
    (net (code "40") (name "Net-(DA1-FBIN)") (class "Default")
      (node (ref "7") (pin "1") (pinfunction "1_1") (pintype "passive"))
      (node (ref "DA1") (pin "15") (pinfunction "FBIN_15") (pintype "passive"))
      (node (ref "R20") (pin "2") (pinfunction "2_2") (pintype "passive"))
      (node (ref "R21") (pin "1") (pinfunction "1_1") (pintype "passive"))
      (node (ref "R24") (pin "1") (pinfunction "1_1") (pintype "passive"))
      (node (ref "R29") (pin "1") (pinfunction "1_1") (pintype "passive"))
    )
    (net (code "41") (name "Net-(DA1-FBIR)") (class "Default")
      (node (ref "DA1") (pin "1") (pinfunction "FBIR_1") (pintype "passive"))
      (node (ref "R21") (pin "2") (pinfunction "2_2") (pintype "passive"))
    )
    (net (code "42") (name "Net-(DA1-FBIW)") (class "Default")
      (node (ref "DA1") (pin "6") (pinfunction "FBIW_6") (pintype "passive"))
      (node (ref "R25") (pin "2") (pinfunction "2_2") (pintype "passive"))
    )
    (net (code "43") (name "Net-(DA1-FBOR)") (class "Default")
      (node (ref "5") (pin "1") (pinfunction "1_1") (pintype "passive"))
      (node (ref "DA1") (pin "16") (pinfunction "FBOUT_16") (pintype "passive"))
      (node (ref "DA1") (pin "57") (pinfunction "FBOR_57") (pintype "passive"))
      (node (ref "R18") (pin "1") (pinfunction "1_1") (pintype "passive"))
      (node (ref "R23") (pin "1") (pinfunction "1_1") (pintype "passive"))
      (node (ref "R27") (pin "2") (pinfunction "2_2") (pintype "passive"))
    )
    (net (code "44") (name "Net-(DA1-FBOW)") (class "Default")
      (node (ref "DA1") (pin "5") (pinfunction "FBOW_5") (pintype "passive"))
      (node (ref "R22") (pin "2") (pinfunction "2_2") (pintype "passive"))
    )
    (net (code "45") (name "Net-(DA1-IIR)") (class "Default")
      (node (ref "C33") (pin "2") (pinfunction "2_2") (pintype "passive"))
      (node (ref "DA1") (pin "10") (pinfunction "IMON_IN_10") (pintype "passive"))
      (node (ref "DA1") (pin "53") (pinfunction "IIR_53") (pintype "passive"))
      (node (ref "R34") (pin "2") (pinfunction "2_2") (pintype "passive"))
    )
    (net (code "46") (name "Net-(DA1-IMON_OUT)") (class "Default")
      (node (ref "C35") (pin "2") (pinfunction "2_2") (pintype "passive"))
      (node (ref "DA1") (pin "17") (pinfunction "IMON_OUT_17") (pintype "passive"))
      (node (ref "R36") (pin "1") (pinfunction "1_1") (pintype "passive"))
      (node (ref "R37") (pin "2") (pinfunction "2_2") (pintype "passive"))
      (node (ref "R44") (pin "2") (pinfunction "2_2") (pintype "passive"))
    )
    (net (code "47") (name "Net-(DA1-IOR)") (class "Default")
      (node (ref "DA1") (pin "64") (pinfunction "IOR_64") (pintype "passive"))
      (node (ref "R36") (pin "2") (pinfunction "2_2") (pintype "passive"))
    )
    (net (code "48") (name "Net-(DA1-IOW)") (class "Default")
      (node (ref "DA1") (pin "50") (pinfunction "IOW_50") (pintype "passive"))
      (node (ref "R37") (pin "1") (pinfunction "1_1") (pintype "passive"))
    )
    (net (code "49") (name "Net-(DA1-MODE)") (class "Default")
      (node (ref "DA1") (pin "9") (pinfunction "MODE_9") (pintype "passive"))
      (node (ref "R40") (pin "2") (pinfunction "2_2") (pintype "passive"))
    )
    (net (code "50") (name "Net-(DA1-RT)") (class "Default")
      (node (ref "DA1") (pin "22") (pinfunction "RT_22") (pintype "passive"))
      (node (ref "R41") (pin "2") (pinfunction "2_2") (pintype "passive"))
    )
    (net (code "51") (name "Net-(DA1-SRVO_FBIN)") (class "Default")
      (node (ref "9") (pin "1") (pinfunction "1_1") (pintype "passive"))
      (node (ref "DA1") (pin "35") (pinfunction "SRVO_FBIN_35") (pintype "passive"))
    )
    (net (code "52") (name "Net-(DA1-SRVO_FBOUT)") (class "Default")
      (node (ref "13") (pin "1") (pinfunction "1_1") (pintype "passive"))
      (node (ref "DA1") (pin "38") (pinfunction "SRVO_FBOUT_38") (pintype "passive"))
    )
    (net (code "53") (name "Net-(DA1-SRVO_IIN)") (class "Default")
      (node (ref "10") (pin "1") (pinfunction "1_1") (pintype "passive"))
      (node (ref "DA1") (pin "36") (pinfunction "SRVO_IIN_36") (pintype "passive"))
    )
    (net (code "54") (name "Net-(DA1-SRVO_IOUT)") (class "Default")
      (node (ref "12") (pin "1") (pinfunction "1_1") (pintype "passive"))
      (node (ref "DA1") (pin "37") (pinfunction "SRVO_IOUT_37") (pintype "passive"))
    )
    (net (code "55") (name "Net-(DA1-SS)") (class "Default")
      (node (ref "C34") (pin "2") (pinfunction "2_2") (pintype "passive"))
      (node (ref "DA1") (pin "19") (pinfunction "SS_19") (pintype "passive"))
    )
    (net (code "56") (name "Net-(DA1-STATUS)") (class "Default")
      (node (ref "DA1") (pin "51") (pinfunction "STATUS_51") (pintype "passive"))
      (node (ref "R31") (pin "1") (pinfunction "1_1") (pintype "passive"))
      (node (ref "VD5") (pin "1") (pinfunction "A_1") (pintype "passive"))
    )
    (net (code "57") (name "Net-(DA1-SWEN)") (class "Default")
      (node (ref "DA1") (pin "49") (pinfunction "SWENO_49") (pintype "passive"))
      (node (ref "DA1") (pin "8") (pinfunction "SWEN_8") (pintype "passive"))
      (node (ref "R26") (pin "1") (pinfunction "1_1") (pintype "passive"))
    )
    (net (code "58") (name "Net-(DA1-SYNC)") (class "Default")
      (node (ref "DA1") (pin "21") (pinfunction "SYNC_21") (pintype "passive"))
      (node (ref "R39") (pin "2") (pinfunction "2_2") (pintype "passive"))
    )
    (net (code "59") (name "Net-(DA1-TEMPSENSE)") (class "Default")
      (node (ref "17") (pin "1") (pinfunction "1_1") (pintype "passive"))
      (node (ref "C38") (pin "2") (pinfunction "2_2") (pintype "passive"))
      (node (ref "DA1") (pin "3") (pinfunction "TEMPSENSE_3") (pintype "passive"))
      (node (ref "R46") (pin "1") (pinfunction "1_1") (pintype "passive"))
      (node (ref "R49") (pin "2") (pinfunction "2_2") (pintype "passive"))
      (node (ref "XT3") (pin "1") (pinfunction "1_1") (pintype "passive"))
    )
    (net (code "60") (name "Net-(DA1-VC)") (class "Default")
      (node (ref "C37") (pin "2") (pinfunction "2_2") (pintype "passive"))
      (node (ref "DA1") (pin "18") (pinfunction "VC_18") (pintype "passive"))
      (node (ref "R47") (pin "2") (pinfunction "2_2") (pintype "passive"))
    )
    (net (code "61") (name "Net-(DA1-~{SHDN})") (class "Default")
      (node (ref "DA1") (pin "11") (pinfunction "~{SHDN}_11") (pintype "passive"))
      (node (ref "R48") (pin "1") (pinfunction "1_1") (pintype "passive"))
      (node (ref "R51") (pin "2") (pinfunction "2_2") (pintype "passive"))
      (node (ref "SB3") (pin "2") (pinfunction "2_2") (pintype "passive"))
    )
    (net (code "62") (name "Net-(DA2-EP)") (class "Default")
      (node (ref "C40") (pin "1") (pinfunction "1_1") (pintype "passive"))
      (node (ref "DA2") (pin "6") (pinfunction "VSS_6") (pintype "passive"))
      (node (ref "DA2") (pin "7") (pinfunction "EP_7") (pintype "passive"))
      (node (ref "R53") (pin "1") (pinfunction "1_1") (pintype "passive"))
      (node (ref "VD8") (pin "2") (pinfunction "C_2") (pintype "passive"))
    )
    (net (code "63") (name "Net-(DA2-GATE)") (class "Default")
      (node (ref "DA2") (pin "2") (pinfunction "GATE_2") (pintype "passive"))
      (node (ref "VD6") (pin "2") (pinfunction "C_2") (pintype "passive"))
      (node (ref "VT6") (pin "4") (pinfunction "G_4") (pintype "passive"))
    )
    (net (code "64") (name "Net-(DA3-CB)") (class "Default")
      (node (ref "C41") (pin "2") (pinfunction "2_2") (pintype "passive"))
      (node (ref "DA3") (pin "1") (pinfunction "CB_1") (pintype "power_in"))
    )
    (net (code "65") (name "Net-(DA3-FB)") (class "Default")
      (node (ref "DA3") (pin "3") (pinfunction "FB_3") (pintype "power_in"))
      (node (ref "R56") (pin "1") (pinfunction "1_1") (pintype "passive"))
      (node (ref "R59") (pin "2") (pinfunction "2_2") (pintype "passive"))
    )
    (net (code "66") (name "Net-(DA3-SW)") (class "Default")
      (node (ref "C41") (pin "1") (pinfunction "1_1") (pintype "passive"))
      (node (ref "DA3") (pin "6") (pinfunction "SW_6") (pintype "power_in"))
      (node (ref "L2") (pin "2") (pinfunction "2_2") (pintype "passive"))
      (node (ref "VD10") (pin "2") (pinfunction "2_2") (pintype "passive"))
    )
    (net (code "67") (name "Net-(DA3-VIN)") (class "Default")
      (node (ref "C42") (pin "2") (pinfunction "2_2") (pintype "passive"))
      (node (ref "C43") (pin "2") (pinfunction "2_2") (pintype "passive"))
      (node (ref "DA3") (pin "5") (pinfunction "VIN_5") (pintype "power_in"))
      (node (ref "VD19") (pin "2") (pinfunction "2_2") (pintype "passive"))
      (node (ref "VD20") (pin "2") (pinfunction "2_2") (pintype "passive"))
    )
    (net (code "68") (name "Net-(R13-Pad1)") (class "Default")
      (node (ref "R13") (pin "1") (pinfunction "1_1") (pintype "passive"))
      (node (ref "VD3") (pin "1") (pinfunction "1_1") (pintype "passive"))
      (node (ref "VD4") (pin "1") (pinfunction "1_1") (pintype "passive"))
    )
    (net (code "69") (name "Net-(R17-Pad2)") (class "Default")
      (node (ref "R17") (pin "2") (pinfunction "2_2") (pintype "passive"))
      (node (ref "R20") (pin "1") (pinfunction "1_1") (pintype "passive"))
    )
    (net (code "70") (name "Net-(VD5-C)") (class "Default")
      (node (ref "R33") (pin "2") (pinfunction "2_2") (pintype "passive"))
      (node (ref "VD5") (pin "2") (pinfunction "C_2") (pintype "passive"))
    )
    (net (code "71") (name "Net-(VD7-A)") (class "Default")
      (node (ref "VD7") (pin "1") (pinfunction "A_1") (pintype "passive"))
      (node (ref "VD8") (pin "1") (pinfunction "A_1") (pintype "passive"))
    )
    (net (code "72") (name "Net-(VD9-C)") (class "Default")
      (node (ref "R57") (pin "2") (pinfunction "2_2") (pintype "passive"))
      (node (ref "VD9") (pin "2") (pinfunction "C_2") (pintype "passive"))
    )
    (net (code "73") (name "Net-(VD20-Pad1)") (class "Default")
      (node (ref "VD20") (pin "1") (pinfunction "1_1") (pintype "passive"))
      (node (ref "XT6") (pin "1") (pinfunction "1_1") (pintype "passive"))
    )
    (net (code "74") (name "Net-(VT1-G)") (class "Default")
      (node (ref "R8") (pin "2") (pinfunction "2_2") (pintype "passive"))
      (node (ref "VT1") (pin "4") (pinfunction "G_4") (pintype "passive"))
    )
    (net (code "75") (name "Net-(VT2-G)") (class "Default")
      (node (ref "R11") (pin "2") (pinfunction "2_2") (pintype "passive"))
      (node (ref "VT2") (pin "4") (pinfunction "G_4") (pintype "passive"))
    )
    (net (code "76") (name "Net-(VT3-G)") (class "Default")
      (node (ref "R9") (pin "2") (pinfunction "2_2") (pintype "passive"))
      (node (ref "VT3") (pin "4") (pinfunction "G_4") (pintype "passive"))
    )
    (net (code "77") (name "Net-(VT4-G)") (class "Default")
      (node (ref "R10") (pin "2") (pinfunction "2_2") (pintype "passive"))
      (node (ref "VT4") (pin "4") (pinfunction "G_4") (pintype "passive"))
    )
    (net (code "78") (name "Net-(VT5-B)") (class "Default")
      (node (ref "R50") (pin "1") (pinfunction "1_1") (pintype "passive"))
      (node (ref "R52") (pin "2") (pinfunction "2_2") (pintype "passive"))
      (node (ref "VT5") (pin "1") (pinfunction "B_1") (pintype "passive"))
    )
    (net (code "79") (name "VBAT") (class "Default")
      (node (ref "FU1") (pin "1") (pinfunction "1_1") (pintype "passive"))
      (node (ref "JP4") (pin "3") (pinfunction "3_3") (pintype "passive"))
      (node (ref "R18") (pin "2") (pinfunction "2_2") (pintype "passive"))
      (node (ref "VD1") (pin "5") (pinfunction "C_5") (pintype "passive"))
      (node (ref "VD1") (pin "8") (pinfunction "C_8") (pintype "passive"))
      (node (ref "XP2") (pin "1") (pintype "passive"))
    )
    (net (code "80") (name "VDD") (class "Default")
      (node (ref "11") (pin "1") (pinfunction "1_1") (pintype "passive"))
      (node (ref "C31") (pin "2") (pinfunction "2_2") (pintype "passive"))
      (node (ref "DA1") (pin "14") (pinfunction "LDO33_14") (pintype "passive"))
      (node (ref "DA1") (pin "4") (pinfunction "VDD_4") (pintype "passive"))
      (node (ref "R30") (pin "2") (pinfunction "2_2") (pintype "passive"))
      (node (ref "R31") (pin "2") (pinfunction "2_2") (pintype "passive"))
      (node (ref "R32") (pin "1") (pinfunction "1_1") (pintype "passive"))
      (node (ref "R35") (pin "1") (pinfunction "1_1") (pintype "passive"))
      (node (ref "R38") (pin "1") (pinfunction "1_1") (pintype "passive"))
      (node (ref "R46") (pin "2") (pinfunction "2_2") (pintype "passive"))
    )
    (net (code "81") (name "VIN") (class "Default")
      (node (ref "C25") (pin "2") (pinfunction "2_2") (pintype "passive"))
      (node (ref "DA1") (pin "46") (pinfunction "VIN_46") (pintype "passive"))
      (node (ref "R16") (pin "2") (pinfunction "2_2") (pintype "passive"))
      (node (ref "R17") (pin "1") (pinfunction "1_1") (pintype "passive"))
      (node (ref "R19") (pin "1") (pinfunction "1_1") (pintype "passive"))
      (node (ref "R48") (pin "2") (pinfunction "2_2") (pintype "passive"))
    )
    (net (code "82") (name "VIN1") (class "Default")
      (node (ref "1") (pin "1") (pinfunction "1_1") (pintype "passive"))
      (node (ref "C1") (pin "1") (pinfunction "1_1") (pintype "power_in"))
      (node (ref "C16") (pin "1") (pinfunction "1_1") (pintype "passive"))
      (node (ref "C17") (pin "2") (pinfunction "2_2") (pintype "passive"))
      (node (ref "C2") (pin "1") (pinfunction "1_1") (pintype "power_in"))
      (node (ref "C3") (pin "1") (pinfunction "1_1") (pintype "power_in"))
      (node (ref "C4") (pin "2") (pinfunction "2_2") (pintype "passive"))
      (node (ref "C40") (pin "2") (pinfunction "2_2") (pintype "passive"))
      (node (ref "C5") (pin "2") (pinfunction "2_2") (pintype "passive"))
      (node (ref "DA1") (pin "45") (pinfunction "CSPIN_45") (pintype "passive"))
      (node (ref "DA2") (pin "1") (pinfunction "OUT_1") (pintype "passive"))
      (node (ref "JP4") (pin "1") (pinfunction "1_1") (pintype "passive"))
      (node (ref "R1") (pin "2") (pinfunction "2_2") (pintype "passive"))
      (node (ref "R16") (pin "1") (pinfunction "1_1") (pintype "passive"))
      (node (ref "VD2") (pin "2") (pinfunction "C_2") (pintype "passive"))
      (node (ref "VT6") (pin "5") (pinfunction "D_5") (pintype "passive"))
      (node (ref "VT6") (pin "6") (pinfunction "D_6") (pintype "passive"))
      (node (ref "VT6") (pin "7") (pinfunction "D_7") (pintype "passive"))
      (node (ref "VT6") (pin "8") (pinfunction "D_8") (pintype "passive"))
      (node (ref "XP1") (pin "1") (pintype "passive"))
      (node (ref "XT1") (pin "1") (pinfunction "1_1") (pintype "passive"))
    )
    (net (code "83") (name "unconnected-(DA1-ECON-Pad48)") (class "Default")
      (node (ref "DA1") (pin "48") (pinfunction "ECON_48") (pintype "passive+no_connect"))
    )
    (net (code "84") (name "unconnected-(DA2-~{SHDN}-Pad5)") (class "Default")
      (node (ref "DA2") (pin "5") (pinfunction "~{SHDN}_5") (pintype "passive+no_connect"))
    )
    (net (code "85") (name "unconnected-(DA3-SHDN-Pad4)") (class "Default")
      (node (ref "DA3") (pin "4") (pinfunction "SHDN_4") (pintype "power_in+no_connect"))
    )
  )
)
